# ESP32_Schem_V2.net
KiCad netlist of a schematic drawn in Altium Designer
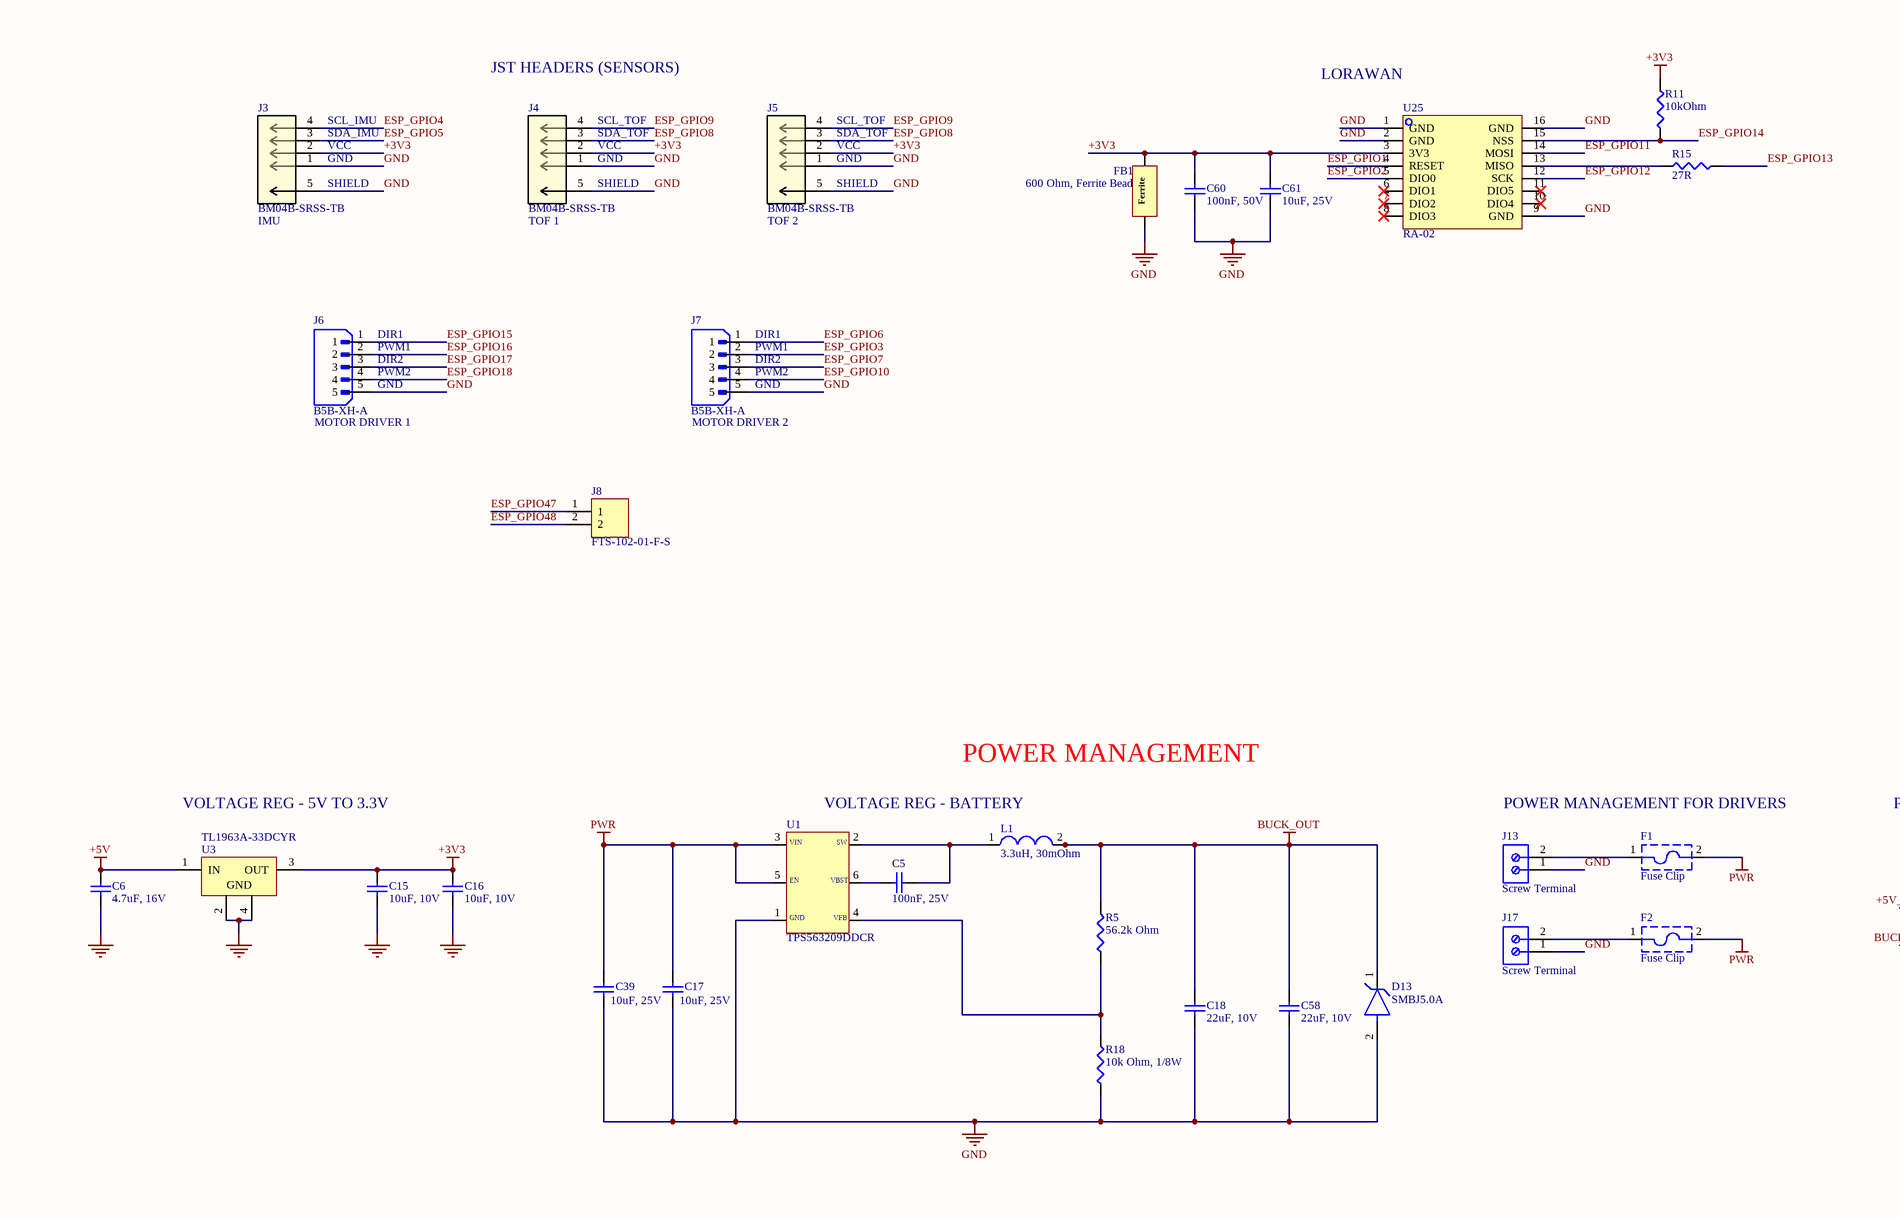
[diagram p0: ESP32_Schem_V2.SchDoc, top left]
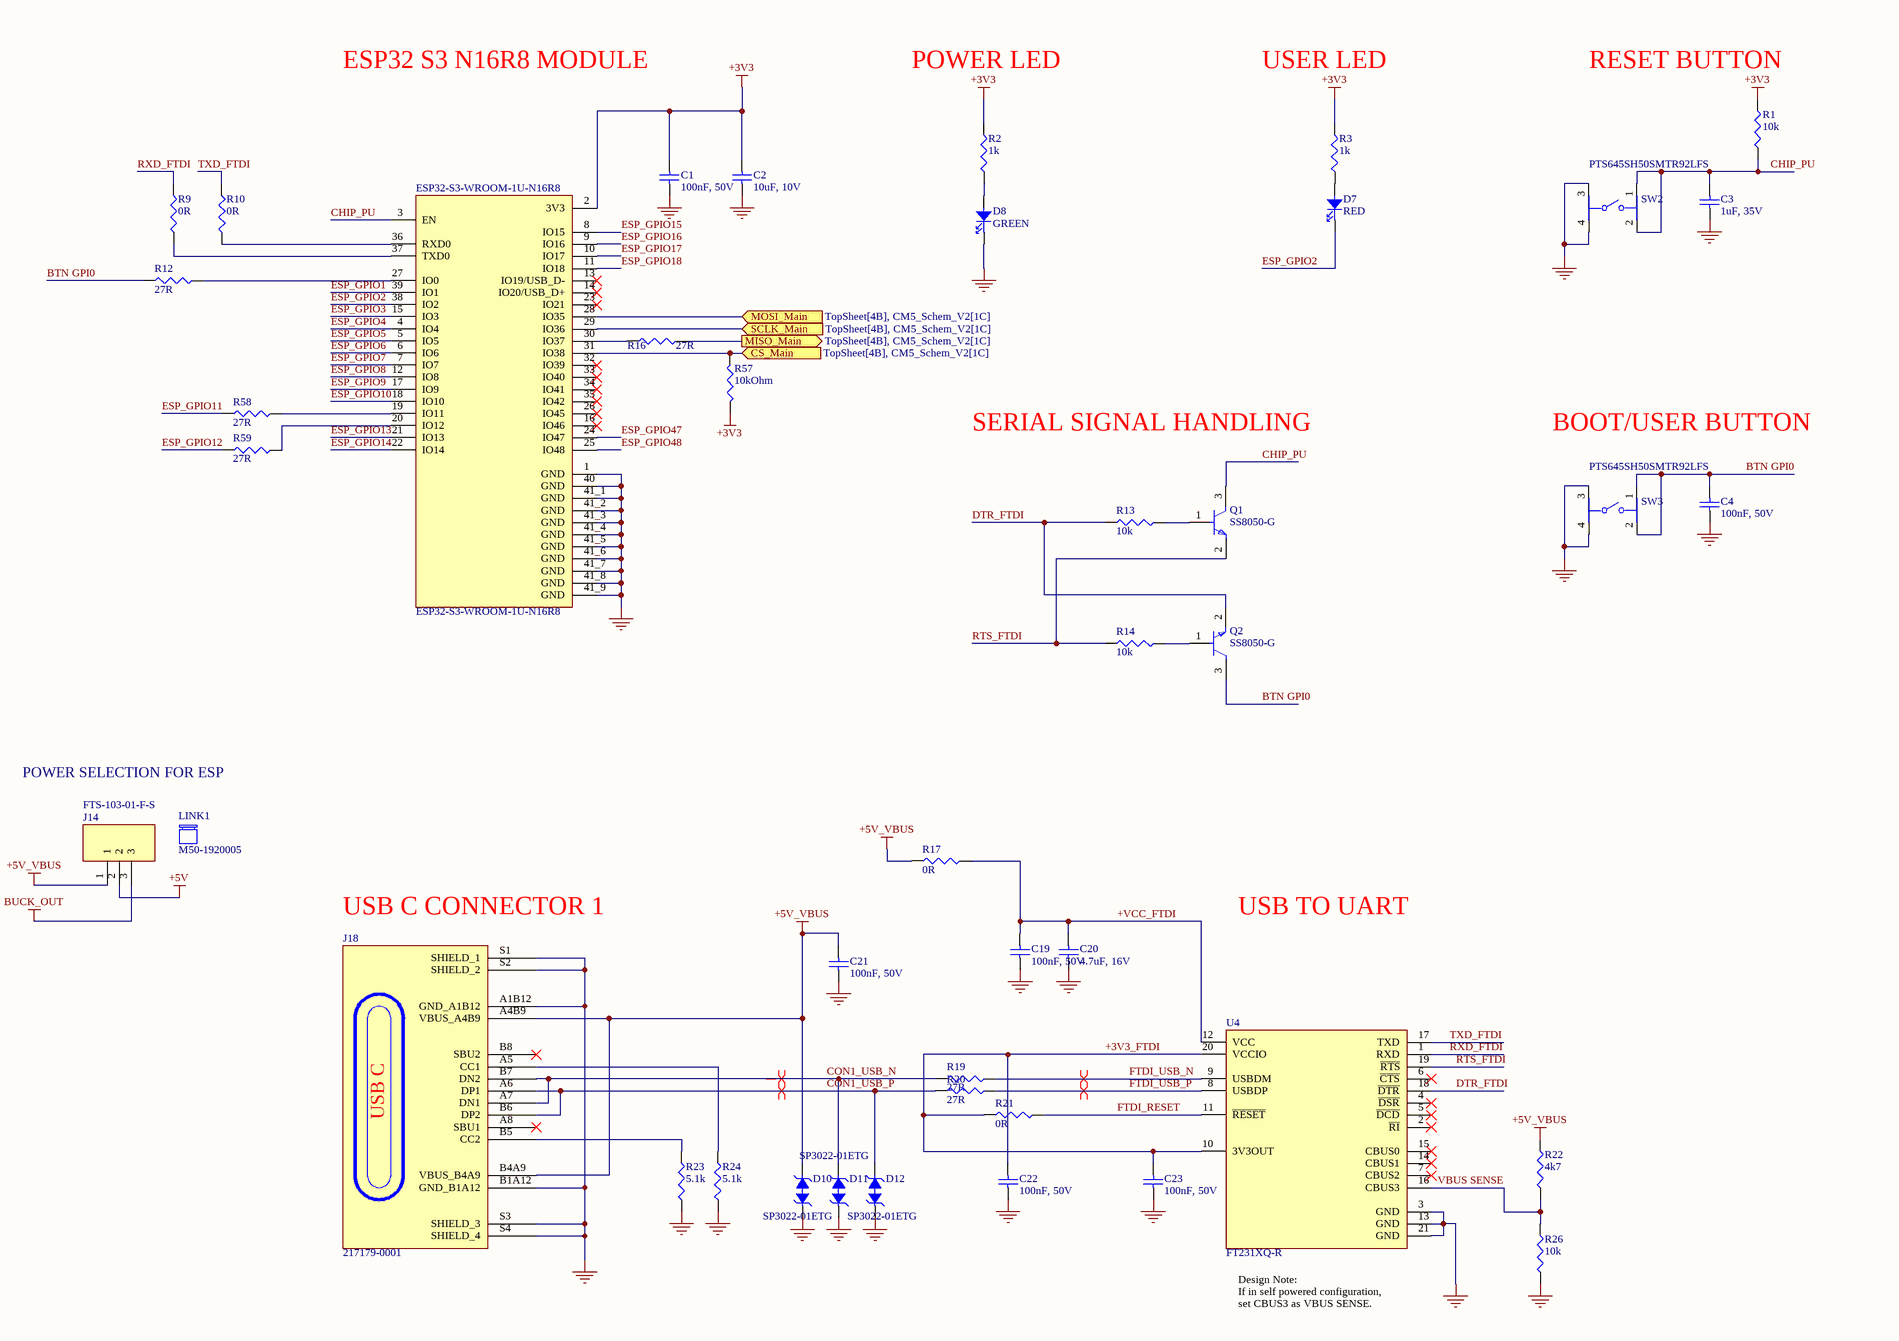
[diagram p1: ESP32_Schem_V2.SchDoc, top right]
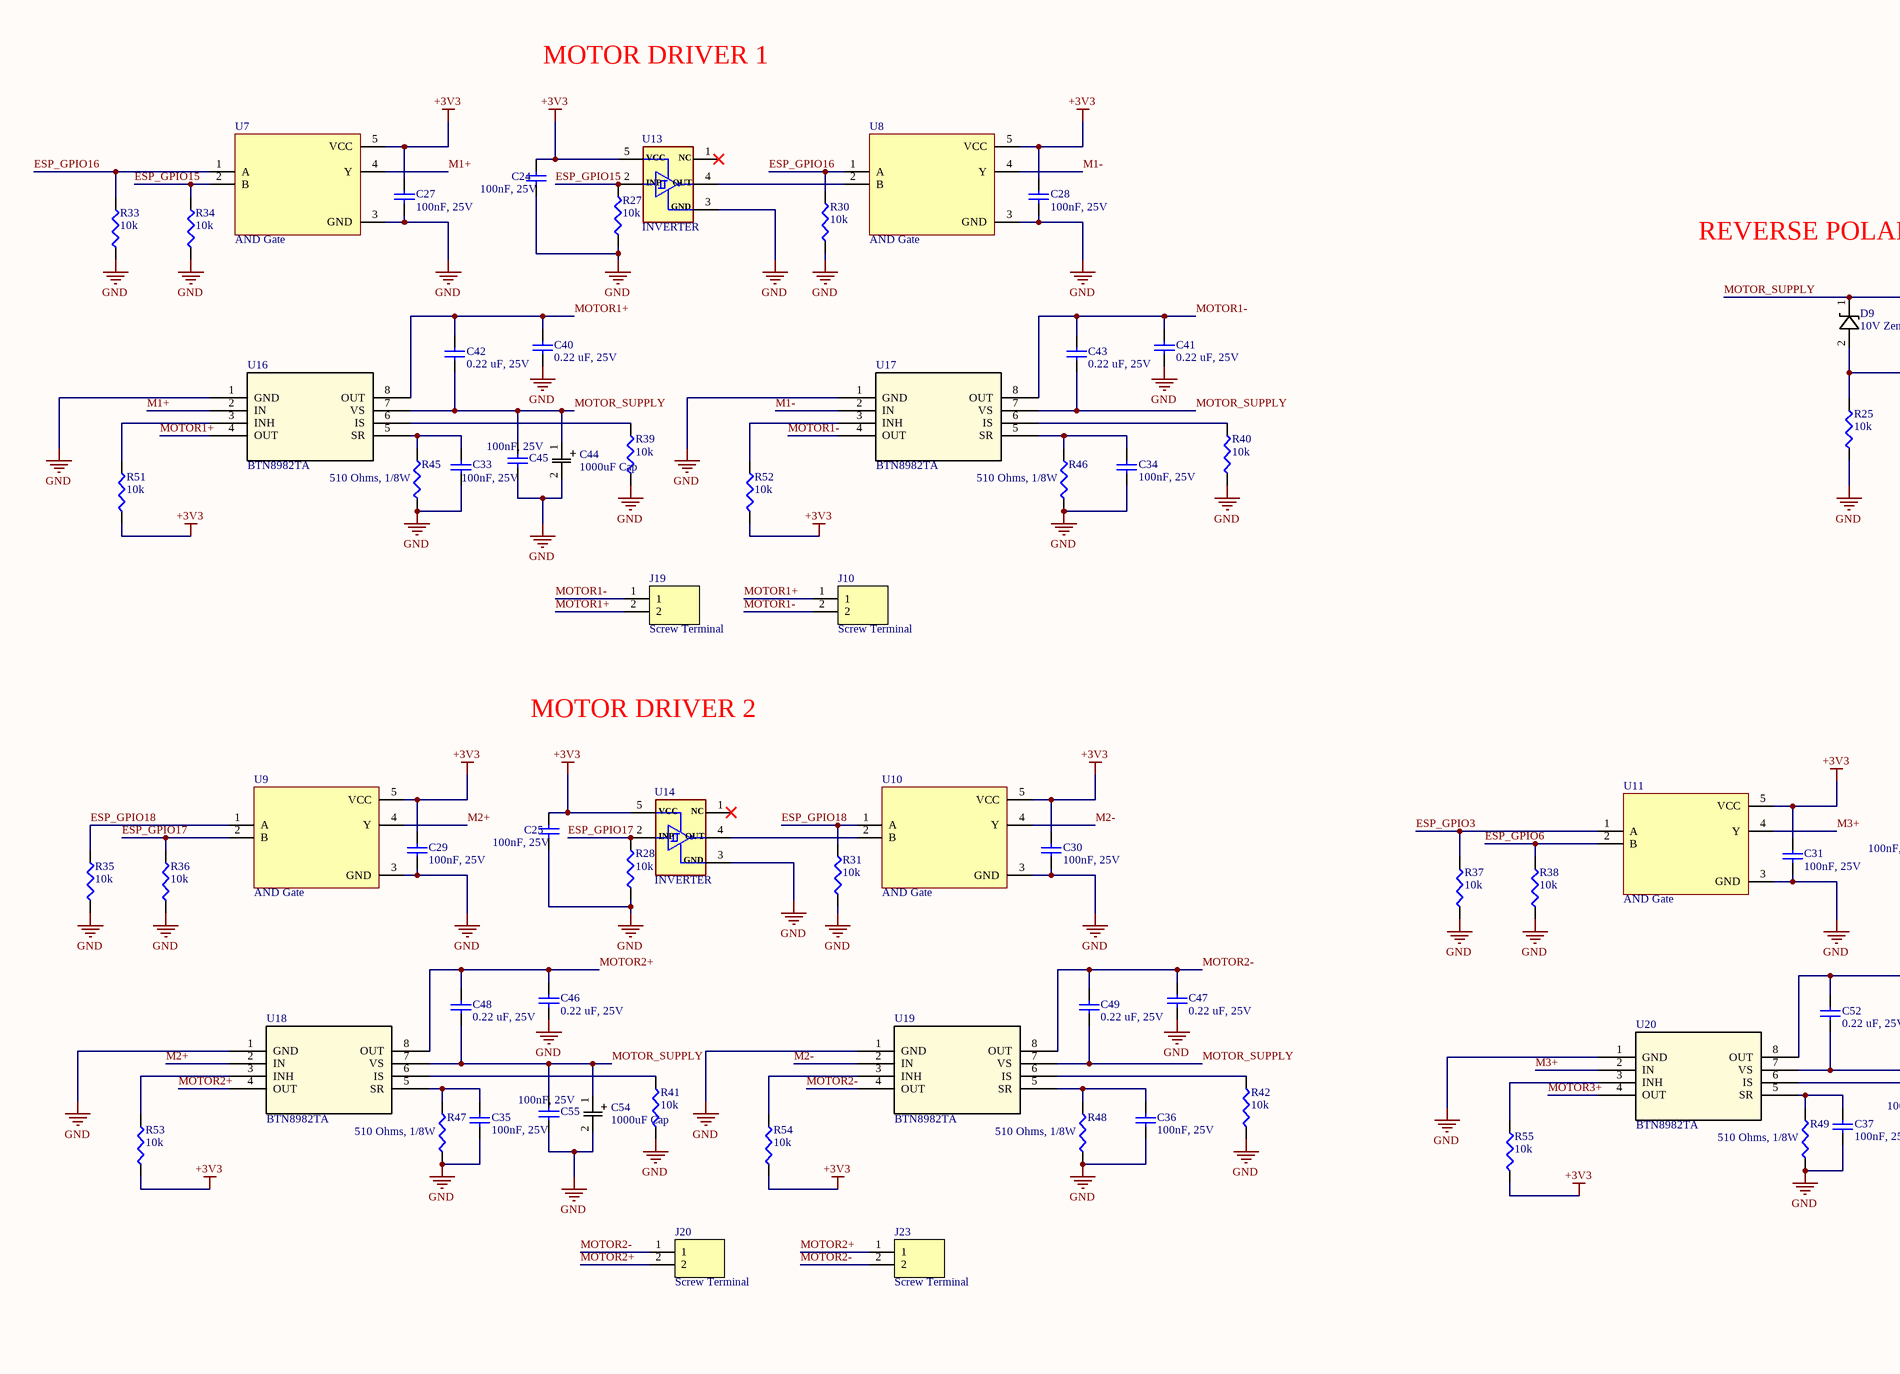
[diagram p2: ESP32_Schem_V2.SchDoc, bottom left]
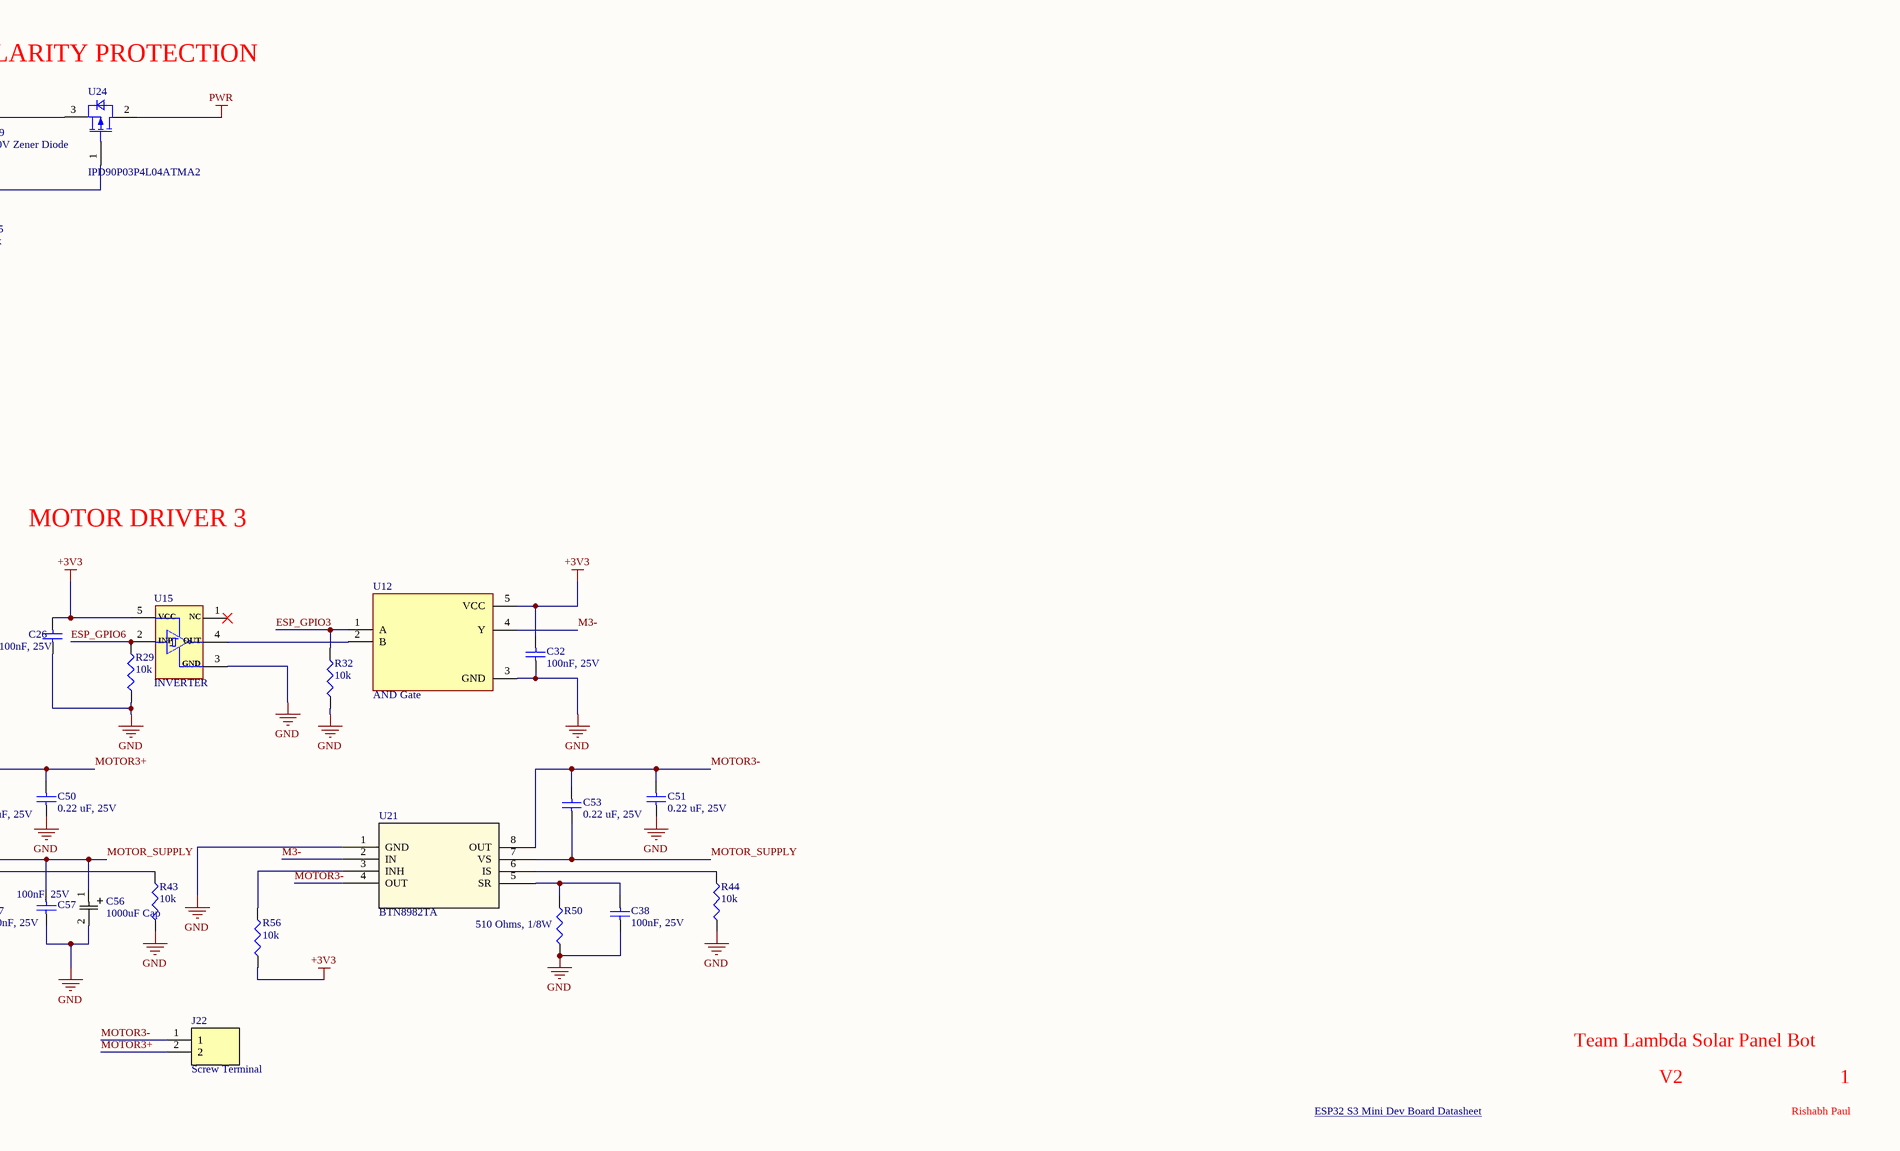
[diagram p3: ESP32_Schem_V2.SchDoc, bottom right]

(export (version "E")
  (design (tool "Eeschema 10.0.6"))
  (components
    (comp (ref "C1")
      (value "100nF, 50V")
      (footprint "CAPC1005X55N")
      (fields
        (field (name "MANUFACTURER") "Samsung")
        (field (name "MANUFACTURER PART NUMBER") "CL05B104KB54PNC")
        (field (name "LCSC PART NUMBER") "C307331")
      )
      (libsource (lib "Schlib") (part "CL05B104KB54PNC"))
    )
    (comp (ref "C2")
      (value "10uF, 10V")
      (footprint "CAPC1005X55N")
      (fields
        (field (name "MANUFACTURER") "Samsung")
        (field (name "MANUFACTURER PART NUMBER") "CL05A106MP8NUB8")
        (field (name "LCSC PART NUMBER") "C307415")
      )
      (libsource (lib "Schlib") (part "CL05A106MP8NUB8"))
    )
    (comp (ref "C3")
      (value "1uF, 35V")
      (footprint "CAPC1005X55N")
      (fields
        (field (name "MANUFACTURER") "Samsung")
        (field (name "MANUFACTURER PART NUMBER") "CL05A105KL5NRNC")
        (field (name "LCSC PART NUMBER") "C307413")
      )
      (libsource (lib "Schlib") (part "CL05A105KL5NRNC"))
    )
    (comp (ref "C4")
      (value "100nF, 50V")
      (footprint "CAPC1005X55N")
      (fields
        (field (name "MANUFACTURER") "Samsung")
        (field (name "MANUFACTURER PART NUMBER") "CL05B104KB54PNC")
        (field (name "LCSC PART NUMBER") "C307331")
      )
      (libsource (lib "Schlib") (part "CL05B104KB54PNC"))
    )
    (comp (ref "C5")
      (value "100nF, 25V")
      (footprint "CAP_X7R_0805_AVX-M")
      (description "25V 100Nf X7R 10% 0805 Multilayer Ceramic Capacitors Mlcc Smd/Smt Rohs")
      (fields
        (field (name "MANUFACTURER") "Yageo Group")
        (field (name "MANUFACTURER PART NUMBER") "CC0805KRX7R8BB104")
      )
      (libsource (lib "Schlib_CM5+ESP32") (part "CC0805KRX7R8BB104"))
    )
    (comp (ref "C6")
      (value "4.7uF, 16V")
      (footprint "CAPC1005X55N")
      (fields
        (field (name "MANUFACTURER") "Samsung")
        (field (name "MANUFACTURER PART NUMBER") "CL05A475MO5NUNC")
        (field (name "LCSC PART NUMBER") "C318563")
      )
      (libsource (lib "Schlib_PersonalProject") (part "CL05A475MO5NUNC"))
    )
    (comp (ref "C15")
      (value "10uF, 10V")
      (footprint "CAPC1005X55N")
      (fields
        (field (name "MANUFACTURER") "Samsung")
        (field (name "MANUFACTURER PART NUMBER") "CL05A106MP8NUB8")
        (field (name "LCSC PART NUMBER") "C307415")
      )
      (libsource (lib "Schlib_PersonalProject") (part "CL05A106MP8NUB8"))
    )
    (comp (ref "C16")
      (value "10uF, 10V")
      (footprint "CAPC1005X55N")
      (fields
        (field (name "MANUFACTURER") "Samsung")
        (field (name "MANUFACTURER PART NUMBER") "CL05A106MP8NUB8")
        (field (name "LCSC PART NUMBER") "C307415")
      )
      (libsource (lib "Schlib_PersonalProject") (part "CL05A106MP8NUB8"))
    )
    (comp (ref "C17")
      (value "10uF, 25V")
      (footprint "CAPC2012X95N")
      (description "CAP CER 10UF 25V X5R 0805")
      (fields
        (field (name "MANUFACTURER") "TAIYO YUDEN")
        (field (name "MANUFACTURER PART NUMBER") "TMK212BBJ106KG-T")
      )
      (libsource (lib "Schlib_CM5+ESP32") (part "TMK212BBJ106KG-T"))
    )
    (comp (ref "C18")
      (value "22uF, 10V")
      (footprint "CAP_1608_TDK-M")
      (description "CAP CER 22UF 10V X5R 0603")
      (fields
        (field (name "MANUFACTURER") "TDK")
        (field (name "MANUFACTURER PART NUMBER") "C1608X5R1A226M080AC")
      )
      (libsource (lib "Schlib_CM5+ESP32") (part "C1608X5R1A226M080AC"))
    )
    (comp (ref "C19")
      (value "100nF, 50V")
      (footprint "CAPC1005X55N")
      (fields
        (field (name "MANUFACTURER") "Samsung")
        (field (name "MANUFACTURER PART NUMBER") "CL05B104KB54PNC")
        (field (name "LCSC PART NUMBER") "C307331")
      )
      (libsource (lib "Schlib") (part "CL05B104KB54PNC"))
    )
    (comp (ref "C20")
      (value "4.7uF, 16V")
      (footprint "CAPC1005X55N")
      (fields
        (field (name "MANUFACTURER") "Samsung")
        (field (name "MANUFACTURER PART NUMBER") "CL05A475MO5NUNC")
        (field (name "LCSC PART NUMBER") "C318563")
      )
      (libsource (lib "Schlib") (part "CL05A475MO5NUNC"))
    )
    (comp (ref "C21")
      (value "100nF, 50V")
      (footprint "CAPC1005X55N")
      (fields
        (field (name "MANUFACTURER") "Samsung")
        (field (name "MANUFACTURER PART NUMBER") "CL05B104KB54PNC")
        (field (name "LCSC PART NUMBER") "C307331")
      )
      (libsource (lib "Schlib") (part "CL05B104KB54PNC"))
    )
    (comp (ref "C22")
      (value "100nF, 50V")
      (footprint "CAPC1005X55N")
      (fields
        (field (name "MANUFACTURER") "Samsung")
        (field (name "MANUFACTURER PART NUMBER") "CL05B104KB54PNC")
        (field (name "LCSC PART NUMBER") "C307331")
      )
      (libsource (lib "Schlib") (part "CL05B104KB54PNC"))
    )
    (comp (ref "C23")
      (value "100nF, 50V")
      (footprint "CAPC1005X55N")
      (fields
        (field (name "MANUFACTURER") "Samsung")
        (field (name "MANUFACTURER PART NUMBER") "CL05B104KB54PNC")
        (field (name "LCSC PART NUMBER") "C307331")
      )
      (libsource (lib "Schlib") (part "CL05B104KB54PNC"))
    )
    (comp (ref "C24")
      (value "100nF, 25V")
      (footprint "CAP_X7R_0805_AVX-M")
      (description "25V 100Nf X7R 10% 0805 Multilayer Ceramic Capacitors Mlcc Smd/Smt Rohs")
      (fields
        (field (name "MANUFACTURER") "Yageo Group")
        (field (name "MANUFACTURER PART NUMBER") "CC0805KRX7R8BB104")
      )
      (libsource (lib "Schlib_CM5+ESP32") (part "CC0805KRX7R8BB104"))
    )
    (comp (ref "C25")
      (value "100nF, 25V")
      (footprint "CAP_X7R_0805_AVX-M")
      (description "25V 100Nf X7R 10% 0805 Multilayer Ceramic Capacitors Mlcc Smd/Smt Rohs")
      (fields
        (field (name "MANUFACTURER") "Yageo Group")
        (field (name "MANUFACTURER PART NUMBER") "CC0805KRX7R8BB104")
      )
      (libsource (lib "Schlib_CM5+ESP32") (part "CC0805KRX7R8BB104"))
    )
    (comp (ref "C26")
      (value "100nF, 25V")
      (footprint "CAP_X7R_0805_AVX-M")
      (description "25V 100Nf X7R 10% 0805 Multilayer Ceramic Capacitors Mlcc Smd/Smt Rohs")
      (fields
        (field (name "MANUFACTURER") "Yageo Group")
        (field (name "MANUFACTURER PART NUMBER") "CC0805KRX7R8BB104")
      )
      (libsource (lib "Schlib_CM5+ESP32") (part "CC0805KRX7R8BB104"))
    )
    (comp (ref "C27")
      (value "100nF, 25V")
      (footprint "CAP_X7R_0805_AVX-M")
      (description "25V 100Nf X7R 10% 0805 Multilayer Ceramic Capacitors Mlcc Smd/Smt Rohs")
      (fields
        (field (name "MANUFACTURER") "Yageo Group")
        (field (name "MANUFACTURER PART NUMBER") "CC0805KRX7R8BB104")
      )
      (libsource (lib "Schlib_CM5+ESP32") (part "CC0805KRX7R8BB104"))
    )
    (comp (ref "C28")
      (value "100nF, 25V")
      (footprint "CAP_X7R_0805_AVX-M")
      (description "25V 100Nf X7R 10% 0805 Multilayer Ceramic Capacitors Mlcc Smd/Smt Rohs")
      (fields
        (field (name "MANUFACTURER") "Yageo Group")
        (field (name "MANUFACTURER PART NUMBER") "CC0805KRX7R8BB104")
      )
      (libsource (lib "Schlib_CM5+ESP32") (part "CC0805KRX7R8BB104"))
    )
    (comp (ref "C29")
      (value "100nF, 25V")
      (footprint "CAP_X7R_0805_AVX-M")
      (description "25V 100Nf X7R 10% 0805 Multilayer Ceramic Capacitors Mlcc Smd/Smt Rohs")
      (fields
        (field (name "MANUFACTURER") "Yageo Group")
        (field (name "MANUFACTURER PART NUMBER") "CC0805KRX7R8BB104")
      )
      (libsource (lib "Schlib_CM5+ESP32") (part "CC0805KRX7R8BB104"))
    )
    (comp (ref "C30")
      (value "100nF, 25V")
      (footprint "CAP_X7R_0805_AVX-M")
      (description "25V 100Nf X7R 10% 0805 Multilayer Ceramic Capacitors Mlcc Smd/Smt Rohs")
      (fields
        (field (name "MANUFACTURER") "Yageo Group")
        (field (name "MANUFACTURER PART NUMBER") "CC0805KRX7R8BB104")
      )
      (libsource (lib "Schlib_CM5+ESP32") (part "CC0805KRX7R8BB104"))
    )
    (comp (ref "C31")
      (value "100nF, 25V")
      (footprint "CAP_X7R_0805_AVX-M")
      (description "25V 100Nf X7R 10% 0805 Multilayer Ceramic Capacitors Mlcc Smd/Smt Rohs")
      (fields
        (field (name "MANUFACTURER") "Yageo Group")
        (field (name "MANUFACTURER PART NUMBER") "CC0805KRX7R8BB104")
      )
      (libsource (lib "Schlib_CM5+ESP32") (part "CC0805KRX7R8BB104"))
    )
    (comp (ref "C32")
      (value "100nF, 25V")
      (footprint "CAP_X7R_0805_AVX-M")
      (description "25V 100Nf X7R 10% 0805 Multilayer Ceramic Capacitors Mlcc Smd/Smt Rohs")
      (fields
        (field (name "MANUFACTURER") "Yageo Group")
        (field (name "MANUFACTURER PART NUMBER") "CC0805KRX7R8BB104")
      )
      (libsource (lib "Schlib_CM5+ESP32") (part "CC0805KRX7R8BB104"))
    )
    (comp (ref "C33")
      (value "100nF, 25V")
      (footprint "CAP_X7R_0805_AVX-M")
      (description "25V 100Nf X7R 10% 0805 Multilayer Ceramic Capacitors Mlcc Smd/Smt Rohs")
      (fields
        (field (name "MANUFACTURER") "Yageo Group")
        (field (name "MANUFACTURER PART NUMBER") "CC0805KRX7R8BB104")
      )
      (libsource (lib "Schlib_CM5+ESP32") (part "CC0805KRX7R8BB104"))
    )
    (comp (ref "C34")
      (value "100nF, 25V")
      (footprint "CAP_X7R_0805_AVX-M")
      (description "25V 100Nf X7R 10% 0805 Multilayer Ceramic Capacitors Mlcc Smd/Smt Rohs")
      (fields
        (field (name "MANUFACTURER") "Yageo Group")
        (field (name "MANUFACTURER PART NUMBER") "CC0805KRX7R8BB104")
      )
      (libsource (lib "Schlib_CM5+ESP32") (part "CC0805KRX7R8BB104"))
    )
    (comp (ref "C35")
      (value "100nF, 25V")
      (footprint "CAP_X7R_0805_AVX-M")
      (description "25V 100Nf X7R 10% 0805 Multilayer Ceramic Capacitors Mlcc Smd/Smt Rohs")
      (fields
        (field (name "MANUFACTURER") "Yageo Group")
        (field (name "MANUFACTURER PART NUMBER") "CC0805KRX7R8BB104")
      )
      (libsource (lib "Schlib_CM5+ESP32") (part "CC0805KRX7R8BB104"))
    )
    (comp (ref "C36")
      (value "100nF, 25V")
      (footprint "CAP_X7R_0805_AVX-M")
      (description "25V 100Nf X7R 10% 0805 Multilayer Ceramic Capacitors Mlcc Smd/Smt Rohs")
      (fields
        (field (name "MANUFACTURER") "Yageo Group")
        (field (name "MANUFACTURER PART NUMBER") "CC0805KRX7R8BB104")
      )
      (libsource (lib "Schlib_CM5+ESP32") (part "CC0805KRX7R8BB104"))
    )
    (comp (ref "C37")
      (value "100nF, 25V")
      (footprint "CAP_X7R_0805_AVX-M")
      (description "25V 100Nf X7R 10% 0805 Multilayer Ceramic Capacitors Mlcc Smd/Smt Rohs")
      (fields
        (field (name "MANUFACTURER") "Yageo Group")
        (field (name "MANUFACTURER PART NUMBER") "CC0805KRX7R8BB104")
      )
      (libsource (lib "Schlib_CM5+ESP32") (part "CC0805KRX7R8BB104"))
    )
    (comp (ref "C38")
      (value "100nF, 25V")
      (footprint "CAP_X7R_0805_AVX-M")
      (description "25V 100Nf X7R 10% 0805 Multilayer Ceramic Capacitors Mlcc Smd/Smt Rohs")
      (fields
        (field (name "MANUFACTURER") "Yageo Group")
        (field (name "MANUFACTURER PART NUMBER") "CC0805KRX7R8BB104")
      )
      (libsource (lib "Schlib_CM5+ESP32") (part "CC0805KRX7R8BB104"))
    )
    (comp (ref "C39")
      (value "10uF, 25V")
      (footprint "CAPC2012X95N")
      (description "CAP CER 10UF 25V X5R 0805")
      (fields
        (field (name "MANUFACTURER") "TAIYO YUDEN")
        (field (name "MANUFACTURER PART NUMBER") "TMK212BBJ106KG-T")
      )
      (libsource (lib "Schlib_CM5+ESP32") (part "TMK212BBJ106KG-T"))
    )
    (comp (ref "C40")
      (value "0.22 uF, 25V")
      (footprint "CAP_1608_TDK-M")
      (description "CAP CER 0.22UF 25V X7R 0603")
      (fields
        (field (name "MANUFACTURER") "Yageo Group")
        (field (name "MANUFACTURER PART NUMBER") "CC0603KRX7R8BB224")
      )
      (libsource (lib "Schlib_CM5+ESP32") (part "CC0603KRX7R8BB224"))
    )
    (comp (ref "C41")
      (value "0.22 uF, 25V")
      (footprint "CAP_1608_TDK-M")
      (description "CAP CER 0.22UF 25V X7R 0603")
      (fields
        (field (name "MANUFACTURER") "Yageo Group")
        (field (name "MANUFACTURER PART NUMBER") "CC0603KRX7R8BB224")
      )
      (libsource (lib "Schlib_CM5+ESP32") (part "CC0603KRX7R8BB224"))
    )
    (comp (ref "C42")
      (value "0.22 uF, 25V")
      (footprint "CAP_1608_TDK-M")
      (description "CAP CER 0.22UF 25V X7R 0603")
      (fields
        (field (name "MANUFACTURER") "Yageo Group")
        (field (name "MANUFACTURER PART NUMBER") "CC0603KRX7R8BB224")
      )
      (libsource (lib "Schlib_CM5+ESP32") (part "CC0603KRX7R8BB224"))
    )
    (comp (ref "C43")
      (value "0.22 uF, 25V")
      (footprint "CAP_1608_TDK-M")
      (description "CAP CER 0.22UF 25V X7R 0603")
      (fields
        (field (name "MANUFACTURER") "Yageo Group")
        (field (name "MANUFACTURER PART NUMBER") "CC0603KRX7R8BB224")
      )
      (libsource (lib "Schlib_CM5+ESP32") (part "CC0603KRX7R8BB224"))
    )
    (comp (ref "C44")
      (value "1000uF Cap")
      (footprint "CAP_PKPZ_10X20_LOW_RUB")
      (description "CAP ALUM 1000UF 20% 35V RADIAL")
      (fields
        (field (name "MANUFACTURER") "Rubycon")
        (field (name "MANUFACTURER PART NUMBER") "35PX1000MEFC10X20")
      )
      (libsource (lib "Schlib_CM5+ESP32") (part "35PX1000MEFC10X20"))
    )
    (comp (ref "C45")
      (value "100nF, 25V")
      (footprint "CAP_X7R_0805_AVX-M")
      (description "25V 100Nf X7R 10% 0805 Multilayer Ceramic Capacitors Mlcc Smd/Smt Rohs")
      (fields
        (field (name "MANUFACTURER") "Yageo Group")
        (field (name "MANUFACTURER PART NUMBER") "CC0805KRX7R8BB104")
      )
      (libsource (lib "Schlib_CM5+ESP32") (part "CC0805KRX7R8BB104"))
    )
    (comp (ref "C46")
      (value "0.22 uF, 25V")
      (footprint "CAP_1608_TDK-M")
      (description "CAP CER 0.22UF 25V X7R 0603")
      (fields
        (field (name "MANUFACTURER") "Yageo Group")
        (field (name "MANUFACTURER PART NUMBER") "CC0603KRX7R8BB224")
      )
      (libsource (lib "Schlib_CM5+ESP32") (part "CC0603KRX7R8BB224"))
    )
    (comp (ref "C47")
      (value "0.22 uF, 25V")
      (footprint "CAP_1608_TDK-M")
      (description "CAP CER 0.22UF 25V X7R 0603")
      (fields
        (field (name "MANUFACTURER") "Yageo Group")
        (field (name "MANUFACTURER PART NUMBER") "CC0603KRX7R8BB224")
      )
      (libsource (lib "Schlib_CM5+ESP32") (part "CC0603KRX7R8BB224"))
    )
    (comp (ref "C48")
      (value "0.22 uF, 25V")
      (footprint "CAP_1608_TDK-M")
      (description "CAP CER 0.22UF 25V X7R 0603")
      (fields
        (field (name "MANUFACTURER") "Yageo Group")
        (field (name "MANUFACTURER PART NUMBER") "CC0603KRX7R8BB224")
      )
      (libsource (lib "Schlib_CM5+ESP32") (part "CC0603KRX7R8BB224"))
    )
    (comp (ref "C49")
      (value "0.22 uF, 25V")
      (footprint "CAP_1608_TDK-M")
      (description "CAP CER 0.22UF 25V X7R 0603")
      (fields
        (field (name "MANUFACTURER") "Yageo Group")
        (field (name "MANUFACTURER PART NUMBER") "CC0603KRX7R8BB224")
      )
      (libsource (lib "Schlib_CM5+ESP32") (part "CC0603KRX7R8BB224"))
    )
    (comp (ref "C50")
      (value "0.22 uF, 25V")
      (footprint "CAP_1608_TDK-M")
      (description "CAP CER 0.22UF 25V X7R 0603")
      (fields
        (field (name "MANUFACTURER") "Yageo Group")
        (field (name "MANUFACTURER PART NUMBER") "CC0603KRX7R8BB224")
      )
      (libsource (lib "Schlib_CM5+ESP32") (part "CC0603KRX7R8BB224"))
    )
    (comp (ref "C51")
      (value "0.22 uF, 25V")
      (footprint "CAP_1608_TDK-M")
      (description "CAP CER 0.22UF 25V X7R 0603")
      (fields
        (field (name "MANUFACTURER") "Yageo Group")
        (field (name "MANUFACTURER PART NUMBER") "CC0603KRX7R8BB224")
      )
      (libsource (lib "Schlib_CM5+ESP32") (part "CC0603KRX7R8BB224"))
    )
    (comp (ref "C52")
      (value "0.22 uF, 25V")
      (footprint "CAP_1608_TDK-M")
      (description "CAP CER 0.22UF 25V X7R 0603")
      (fields
        (field (name "MANUFACTURER") "Yageo Group")
        (field (name "MANUFACTURER PART NUMBER") "CC0603KRX7R8BB224")
      )
      (libsource (lib "Schlib_CM5+ESP32") (part "CC0603KRX7R8BB224"))
    )
    (comp (ref "C53")
      (value "0.22 uF, 25V")
      (footprint "CAP_1608_TDK-M")
      (description "CAP CER 0.22UF 25V X7R 0603")
      (fields
        (field (name "MANUFACTURER") "Yageo Group")
        (field (name "MANUFACTURER PART NUMBER") "CC0603KRX7R8BB224")
      )
      (libsource (lib "Schlib_CM5+ESP32") (part "CC0603KRX7R8BB224"))
    )
    (comp (ref "C54")
      (value "1000uF Cap")
      (footprint "CAP_PKPZ_10X20_LOW_RUB")
      (description "CAP ALUM 1000UF 20% 35V RADIAL")
      (fields
        (field (name "MANUFACTURER") "Rubycon")
        (field (name "MANUFACTURER PART NUMBER") "35PX1000MEFC10X20")
      )
      (libsource (lib "Schlib_CM5+ESP32") (part "35PX1000MEFC10X20"))
    )
    (comp (ref "C55")
      (value "100nF, 25V")
      (footprint "CAP_X7R_0805_AVX-M")
      (description "25V 100Nf X7R 10% 0805 Multilayer Ceramic Capacitors Mlcc Smd/Smt Rohs")
      (fields
        (field (name "MANUFACTURER") "Yageo Group")
        (field (name "MANUFACTURER PART NUMBER") "CC0805KRX7R8BB104")
      )
      (libsource (lib "Schlib_CM5+ESP32") (part "CC0805KRX7R8BB104"))
    )
    (comp (ref "C56")
      (value "1000uF Cap")
      (footprint "CAP_PKPZ_10X20_LOW_RUB")
      (description "CAP ALUM 1000UF 20% 35V RADIAL")
      (fields
        (field (name "MANUFACTURER") "Rubycon")
        (field (name "MANUFACTURER PART NUMBER") "35PX1000MEFC10X20")
      )
      (libsource (lib "Schlib_CM5+ESP32") (part "35PX1000MEFC10X20"))
    )
    (comp (ref "C57")
      (value "100nF, 25V")
      (footprint "CAP_X7R_0805_AVX-M")
      (description "25V 100Nf X7R 10% 0805 Multilayer Ceramic Capacitors Mlcc Smd/Smt Rohs")
      (fields
        (field (name "MANUFACTURER") "Yageo Group")
        (field (name "MANUFACTURER PART NUMBER") "CC0805KRX7R8BB104")
      )
      (libsource (lib "Schlib_CM5+ESP32") (part "CC0805KRX7R8BB104"))
    )
    (comp (ref "C58")
      (value "22uF, 10V")
      (footprint "CAP_1608_TDK-M")
      (description "CAP CER 22UF 10V X5R 0603")
      (fields
        (field (name "MANUFACTURER") "TDK")
        (field (name "MANUFACTURER PART NUMBER") "C1608X5R1A226M080AC")
      )
      (libsource (lib "Schlib_CM5+ESP32") (part "C1608X5R1A226M080AC"))
    )
    (comp (ref "C60")
      (value "100nF, 50V")
      (footprint "CAPC1005X55N")
      (fields
        (field (name "MANUFACTURER") "Samsung")
        (field (name "MANUFACTURER PART NUMBER") "CL05B104KB54PNC")
        (field (name "LCSC PART NUMBER") "C307331")
      )
      (libsource (lib "Schlib") (part "CL05B104KB54PNC"))
    )
    (comp (ref "C61")
      (value "10uF, 25V")
      (footprint "CAPC2012X95N")
      (description "CAP CER 10UF 25V X5R 0805")
      (fields
        (field (name "MANUFACTURER") "TAIYO YUDEN")
        (field (name "MANUFACTURER PART NUMBER") "TMK212BBJ106KG-T")
      )
      (libsource (lib "Schlib_CM5+ESP32") (part "TMK212BBJ106KG-T"))
    )
    (comp (ref "D7")
      (value "RED")
      (footprint "LED0402R")
      (description "Single Color LED, Super Red, 0.5mm")
      (fields
        (field (name "MANUFACTURER") "Vishay")
        (field (name "MANUFACTURER PART NUMBER") "VLMS1500-GS08")
      )
      (libsource (lib "Schlib") (part "VLMS1500-GS08"))
    )
    (comp (ref "D8")
      (value "GREEN")
      (footprint "LED0402G")
      (description "Single Color LED, Yellow Green, 0.5mm")
      (fields
        (field (name "MANUFACTURER") "Vishay")
        (field (name "MANUFACTURER PART NUMBER") "VLMG1500-GS08")
      )
      (libsource (lib "Schlib") (part "VLMG1500-GS08"))
    )
    (comp (ref "D9")
      (value "10V Zener Diode")
      (footprint "CR_BZT52_DIO")
      (description "Zener Diode, 10V, 0.25W, X1-Dfn1006 Rohs Compliant: Yes ¦Diodes Inc. BZT52C10LP-7")
      (fields
        (field (name "MANUFACTURER") "Diodes Inc.")
        (field (name "MANUFACTURER PART NUMBER") "BZT52C10LP-7")
      )
      (libsource (lib "Schlib_CM5+ESP32") (part "BZT52C10LP-7"))
    )
    (comp (ref "D10")
      (value "SP3022-01ETG")
      (footprint "SOD882")
      (description "TVS DIODE 5.3VWM 12VC SOD882")
      (fields (field (name "MANUFACTURER") "Littelfuse") (field (name "LCSC PART NUMBER") "C126840"))
      (libsource (lib "Schlib_CM5+ESP32") (part "SP3022-01ETG"))
    )
    (comp (ref "D11")
      (value "SP3022-01ETG")
      (footprint "SOD882")
      (description "TVS DIODE 5.3VWM 12VC SOD882")
      (fields (field (name "MANUFACTURER") "Littelfuse") (field (name "LCSC PART NUMBER") "C126840"))
      (libsource (lib "Schlib_CM5+ESP32") (part "SP3022-01ETG"))
    )
    (comp (ref "D12")
      (value "SP3022-01ETG")
      (footprint "SOD882")
      (description "TVS DIODE 5.3VWM 12VC SOD882")
      (fields (field (name "MANUFACTURER") "Littelfuse") (field (name "LCSC PART NUMBER") "C126840"))
      (libsource (lib "Schlib_CM5+ESP32") (part "SP3022-01ETG"))
    )
    (comp (ref "D13")
      (value "SMBJ5.0A")
      (footprint "DO-214AASMB_J-BEND_LTF-M")
      (description "TVS DIODE 5VWM 9.2VC DO214AA")
      (fields (field (name "MANUFACTURER") "Littelfuse") (field (name "LCSC PART NUMBER") "C83333"))
      (libsource (lib "Schlib_CM5+ESP32") (part "SMBJ5.0A"))
    )
    (comp (ref "ESP32-S3-WROOM-1U-N16R8")
      (value "ESP32-S3-WROOM-1U-N16R8")
      (footprint "XCVR_ESP32-S3-WROOM-1U-N16R8")
      (fields (field (name "MANUFACTURER") "Espressif Systems") (field (name "LCSC PART NUMBER") "C49164661"))
      (libsource (lib "Schlib_CM5+ESP32") (part "ESP32-S3-WROOM-1U-N16R8"))
    )
    (comp (ref "F1")
      (value "Fuse Clip")
      (footprint "696108003002")
      (description "Fuses/Accessories")
      (fields
        (field (name "MANUFACTURER") "Wurth Electronics")
        (field (name "MANUFACTURER PART NUMBER") "696108003002")
      )
      (libsource (lib "Schlib_CM5+ESP32") (part "696108003002"))
    )
    (comp (ref "F2")
      (value "Fuse Clip")
      (footprint "696108003002")
      (description "Fuses/Accessories")
      (fields
        (field (name "MANUFACTURER") "Wurth Electronics")
        (field (name "MANUFACTURER PART NUMBER") "696108003002")
      )
      (libsource (lib "Schlib_CM5+ESP32") (part "696108003002"))
    )
    (comp (ref "FB1")
      (value "600 Ohm, Ferrite Bead")
      (footprint "BEADC1608X95N")
      (description "FERRITE BEAD 600 OHM 0603 1LN")
      (fields
        (field (name "MANUFACTURER") "Murata")
        (field (name "MANUFACTURER PART NUMBER") "BLM18AG601SN1D")
      )
      (libsource (lib "Schlib_CM5+ESP32") (part "BLM18AG601SN1D"))
    )
    (comp (ref "J3")
      (value "BM04B-SRSS-TB")
      (footprint "CONN4_BM04B-SRSS_JST")
      (description "CONN HEADER SMD 4POS 1MM")
      (fields (field (name "MANUFACTURER") "JST") (field (name "LCSC PART NUMBER") "C160390"))
      (libsource (lib "Schlib_CM5+ESP32") (part "BM04B-SRSS-TB"))
    )
    (comp (ref "J4")
      (value "BM04B-SRSS-TB")
      (footprint "CONN4_BM04B-SRSS_JST")
      (description "CONN HEADER SMD 4POS 1MM")
      (fields (field (name "MANUFACTURER") "JST") (field (name "LCSC PART NUMBER") "C160390"))
      (libsource (lib "Schlib_CM5+ESP32") (part "BM04B-SRSS-TB"))
    )
    (comp (ref "J5")
      (value "BM04B-SRSS-TB")
      (footprint "CONN4_BM04B-SRSS_JST")
      (description "CONN HEADER SMD 4POS 1MM")
      (fields (field (name "MANUFACTURER") "JST") (field (name "LCSC PART NUMBER") "C160390"))
      (libsource (lib "Schlib_CM5+ESP32") (part "BM04B-SRSS-TB"))
    )
    (comp (ref "J6")
      (value "B5B-XH-A")
      (footprint "JST_B5B-XH-A")
      (description "CONN HEADER VERT 5POS 2.5MM")
      (fields (field (name "MANUFACTURER") "JST") (field (name "LCSC PART NUMBER") "C157991"))
      (libsource (lib "Schlib_CM5+ESP32") (part "B5B-XH-A"))
    )
    (comp (ref "J7")
      (value "B5B-XH-A")
      (footprint "JST_B5B-XH-A")
      (description "CONN HEADER VERT 5POS 2.5MM")
      (fields (field (name "MANUFACTURER") "JST") (field (name "LCSC PART NUMBER") "C157991"))
      (libsource (lib "Schlib_CM5+ESP32") (part "B5B-XH-A"))
    )
    (comp (ref "J8")
      (value "FTS-102-01-F-S")
      (footprint "HDR_1x2_1.27MM")
      (description "Board Connector, 2 Contact(s), 1 Row(s), Male, Straight, Solder Terminal")
      (fields (field (name "MANUFACTURER") "Samtec") (field (name "LCSC PART NUMBER") "C6045317"))
      (libsource (lib "Schlib") (part "FTS-102-01-F-S"))
    )
    (comp (ref "J10")
      (value "Screw Terminal")
      (footprint "CUI_TB005-762-02BE")
      (description "2~24 Poles, Screw Type, Horizontal, 7.62 Pitch, 26~10 (AWG), Terminal Block Connector")
      (fields
        (field (name "MANUFACTURER") "Same Sky")
        (field (name "MANUFACTURER PART NUMBER") "TB005-762-02BE")
      )
      (libsource (lib "Schlib_CM5+ESP32") (part "TB005-762-02BE"))
    )
    (comp (ref "J13")
      (value "Screw Terminal")
      (footprint "PHOENIX_1725656")
      (description "Block, Terminal; 6 A; 63 V; 2.54 mm; 26 to 20 AWG; 2; Screw; Soldering; 1.5 kV")
      (fields
        (field (name "MANUFACTURER") "Phoenix Contact")
        (field (name "MANUFACTURER PART NUMBER") "1725656")
      )
      (libsource (lib "Schlib_CM5+ESP32") (part "1725656"))
    )
    (comp (ref "J14")
      (value "FTS-103-01-F-S")
      (footprint "HDR_1x3_1.27MM")
      (description "Board Connector, 3 Contact(s), 1 Row(s), Male, Straight, Solder Terminal")
      (fields (field (name "MANUFACTURER") "Samtec") (field (name "LCSC PART NUMBER") "C3333578"))
      (libsource (lib "Schlib") (part "FTS-103-01-F-S"))
    )
    (comp (ref "J17")
      (value "Screw Terminal")
      (footprint "PHOENIX_1725656")
      (description "Block, Terminal; 6 A; 63 V; 2.54 mm; 26 to 20 AWG; 2; Screw; Soldering; 1.5 kV")
      (fields
        (field (name "MANUFACTURER") "Phoenix Contact")
        (field (name "MANUFACTURER PART NUMBER") "1725656")
      )
      (libsource (lib "Schlib_CM5+ESP32") (part "1725656"))
    )
    (comp (ref "J18")
      (value "217179-0001")
      (footprint "FP-2171790001-MFG")
      (description "USB Connector, 16 Contact(s), Female, Right Angle, Surface Mount Terminal, Locking, Receptacle")
      (fields (field (name "MANUFACTURER") "Molex") (field (name "LCSC PART NUMBER") "C3197684"))
      (libsource (lib "Schlib") (part "217179-0001"))
    )
    (comp (ref "J19")
      (value "Screw Terminal")
      (footprint "CUI_TB005-762-02BE")
      (description "2~24 Poles, Screw Type, Horizontal, 7.62 Pitch, 26~10 (AWG), Terminal Block Connector")
      (fields
        (field (name "MANUFACTURER") "Same Sky")
        (field (name "MANUFACTURER PART NUMBER") "TB005-762-02BE")
      )
      (libsource (lib "Schlib_CM5+ESP32") (part "TB005-762-02BE"))
    )
    (comp (ref "J20")
      (value "Screw Terminal")
      (footprint "CUI_TB005-762-02BE")
      (description "2~24 Poles, Screw Type, Horizontal, 7.62 Pitch, 26~10 (AWG), Terminal Block Connector")
      (fields
        (field (name "MANUFACTURER") "Same Sky")
        (field (name "MANUFACTURER PART NUMBER") "TB005-762-02BE")
      )
      (libsource (lib "Schlib_CM5+ESP32") (part "TB005-762-02BE"))
    )
    (comp (ref "J22")
      (value "Screw Terminal")
      (footprint "CUI_TB005-762-02BE")
      (description "2~24 Poles, Screw Type, Horizontal, 7.62 Pitch, 26~10 (AWG), Terminal Block Connector")
      (fields
        (field (name "MANUFACTURER") "Same Sky")
        (field (name "MANUFACTURER PART NUMBER") "TB005-762-02BE")
      )
      (libsource (lib "Schlib_CM5+ESP32") (part "TB005-762-02BE"))
    )
    (comp (ref "J23")
      (value "Screw Terminal")
      (footprint "CUI_TB005-762-02BE")
      (description "2~24 Poles, Screw Type, Horizontal, 7.62 Pitch, 26~10 (AWG), Terminal Block Connector")
      (fields
        (field (name "MANUFACTURER") "Same Sky")
        (field (name "MANUFACTURER PART NUMBER") "TB005-762-02BE")
      )
      (libsource (lib "Schlib_CM5+ESP32") (part "TB005-762-02BE"))
    )
    (comp (ref "L1")
      (value "3.3uH, 30mOhm")
      (footprint "IND_VLS6045EX-3R3N")
      (description "FIXED IND 3.3UH 4.95A 30MOHM SMD")
      (fields (field (name "MANUFACTURER") "TDK") (field (name "MANUFACTURER PART NUMBER") "VLS6045EX-3R3N"))
      (libsource (lib "Schlib_CM5+ESP32") (part "VLS6045EX-3R3N"))
    )
    (comp (ref "LINK1")
      (value "M50-1920005")
      (description "Interconnection Device")
      (fields (field (name "MANUFACTURER") "Harwin") (field (name "LCSC PART NUMBER") "C6985646"))
      (libsource (lib "Schlib") (part "M50-1920005"))
    )
    (comp (ref "Q1")
      (value "SS8050-G")
      (footprint "FP-SS8050-G-IPC_B")
      (description "Small Signal Bipolar Transistor, 1.5A I(C), 25V V(BR)CEO, 1-Element, NPN, Silicon")
      (fields (field (name "MANUFACTURER") "Comchip") (field (name "LCSC PART NUMBER") "C164886"))
      (libsource (lib "Schlib") (part "SS8050-G"))
    )
    (comp (ref "Q2")
      (value "SS8050-G")
      (footprint "FP-SS8050-G-IPC_B")
      (description "Small Signal Bipolar Transistor, 1.5A I(C), 25V V(BR)CEO, 1-Element, NPN, Silicon")
      (fields (field (name "MANUFACTURER") "Comchip") (field (name "LCSC PART NUMBER") "C164886"))
      (libsource (lib "Schlib") (part "SS8050-G"))
    )
    (comp (ref "R1")
      (value "10k")
      (footprint "RESC1005X37N")
      (fields
        (field (name "MANUFACTURER") "Yageo")
        (field (name "MANUFACTURER PART NUMBER") "AC0402FR-0710KL")
        (field (name "TOLERANCE") "1%")
      )
      (libsource (lib "Schlib") (part "AC0402FR-0710KL"))
    )
    (comp (ref "R2")
      (value "1k")
      (footprint "RESC1005X37N")
      (fields
        (field (name "MANUFACTURER") "Yageo")
        (field (name "MANUFACTURER PART NUMBER") "RC0402FR-071KL")
        (field (name "TOLERANCE") "1%")
      )
      (libsource (lib "Schlib") (part "RC0402FR-071KL"))
    )
    (comp (ref "R3")
      (value "1k")
      (footprint "RESC1005X37N")
      (fields
        (field (name "MANUFACTURER") "Yageo")
        (field (name "MANUFACTURER PART NUMBER") "RC0402FR-071KL")
        (field (name "TOLERANCE") "1%")
      )
      (libsource (lib "Schlib") (part "RC0402FR-071KL"))
    )
    (comp (ref "R5")
      (value "56.2k Ohm")
      (footprint "RESC0603X26N")
      (description "RES 56.2K OHM 1% 1/20W 0201")
      (fields
        (field (name "MANUFACTURER") "Yageo")
        (field (name "MANUFACTURER PART NUMBER") "RC0201FR-0756K2L")
      )
      (libsource (lib "Schlib_CM5+ESP32") (part "RC0201FR-0756K2L"))
    )
    (comp (ref "R9")
      (value "0R")
      (footprint "RESC1005X37N")
      (description "Fixed Resistor, Metal Glaze/thick Film, 0.0625W, 0ohm, Surface Mount, 0402")
      (fields
        (field (name "MANUFACTURER") "Yageo")
        (field (name "MANUFACTURER PART NUMBER") "RC0402FR-070RL")
      )
      (libsource (lib "Schlib") (part "RC0402FR-070RL"))
    )
    (comp (ref "R10")
      (value "0R")
      (footprint "RESC1005X37N")
      (description "Fixed Resistor, Metal Glaze/thick Film, 0.0625W, 0ohm, Surface Mount, 0402")
      (fields
        (field (name "MANUFACTURER") "Yageo")
        (field (name "MANUFACTURER PART NUMBER") "RC0402FR-070RL")
      )
      (libsource (lib "Schlib") (part "RC0402FR-070RL"))
    )
    (comp (ref "R11")
      (value "10kOhm")
      (footprint "RESC0603X26N - duplicate")
      (description "RES 10K OHM 1% 1/20W 0201")
      (fields
        (field (name "MANUFACTURER") "Yageo")
        (field (name "MANUFACTURER PART NUMBER") "RC0201FR-0710KL")
      )
      (libsource (lib "Schlib_CM5+ESP32") (part "RC0201FR-0710KL"))
    )
    (comp (ref "R12")
      (value "27R")
      (footprint "RESC1005X37N")
      (fields
        (field (name "MANUFACTURER") "Yageo")
        (field (name "MANUFACTURER PART NUMBER") "RC0402FR-0727RL")
        (field (name "TOLERANCE") "1%")
      )
      (libsource (lib "Schlib") (part "RC0402FR-0727RL"))
    )
    (comp (ref "R13")
      (value "10k")
      (footprint "RESC1005X37N")
      (fields
        (field (name "MANUFACTURER") "Yageo")
        (field (name "MANUFACTURER PART NUMBER") "AC0402FR-0710KL")
        (field (name "TOLERANCE") "1%")
      )
      (libsource (lib "Schlib") (part "AC0402FR-0710KL"))
    )
    (comp (ref "R14")
      (value "10k")
      (footprint "RESC1005X37N")
      (fields
        (field (name "MANUFACTURER") "Yageo")
        (field (name "MANUFACTURER PART NUMBER") "AC0402FR-0710KL")
        (field (name "TOLERANCE") "1%")
      )
      (libsource (lib "Schlib") (part "AC0402FR-0710KL"))
    )
    (comp (ref "R15")
      (value "27R")
      (footprint "RESC1005X37N")
      (fields
        (field (name "MANUFACTURER") "Yageo")
        (field (name "MANUFACTURER PART NUMBER") "RC0402FR-0727RL")
        (field (name "TOLERANCE") "1%")
      )
      (libsource (lib "Schlib") (part "RC0402FR-0727RL"))
    )
    (comp (ref "R16")
      (value "27R")
      (footprint "RESC1005X37N")
      (fields
        (field (name "MANUFACTURER") "Yageo")
        (field (name "MANUFACTURER PART NUMBER") "RC0402FR-0727RL")
        (field (name "TOLERANCE") "1%")
      )
      (libsource (lib "Schlib") (part "RC0402FR-0727RL"))
    )
    (comp (ref "R17")
      (value "0R")
      (footprint "RESC1005X37N")
      (description "Fixed Resistor, Metal Glaze/thick Film, 0.0625W, 0ohm, Surface Mount, 0402")
      (fields
        (field (name "MANUFACTURER") "Yageo")
        (field (name "MANUFACTURER PART NUMBER") "RC0402FR-070RL")
      )
      (libsource (lib "Schlib") (part "RC0402FR-070RL"))
    )
    (comp (ref "R18")
      (value "10k Ohm, 1/8W")
      (footprint "RESC1005X40N")
      (description "RES 10K OHM 1% 1/8W 0402")
      (fields
        (field (name "MANUFACTURER") "Yageo Group")
        (field (name "MANUFACTURER PART NUMBER") "RC0402FR-7W10KL")
      )
      (libsource (lib "Schlib_CM5+ESP32") (part "RC0402FR-7W10KL"))
    )
    (comp (ref "R19")
      (value "27R")
      (footprint "RESC1005X37N")
      (fields
        (field (name "MANUFACTURER") "Yageo")
        (field (name "MANUFACTURER PART NUMBER") "RC0402FR-0727RL")
        (field (name "TOLERANCE") "1%")
      )
      (libsource (lib "Schlib") (part "RC0402FR-0727RL"))
    )
    (comp (ref "R20")
      (value "27R")
      (footprint "RESC1005X37N")
      (fields
        (field (name "MANUFACTURER") "Yageo")
        (field (name "MANUFACTURER PART NUMBER") "RC0402FR-0727RL")
        (field (name "TOLERANCE") "1%")
      )
      (libsource (lib "Schlib") (part "RC0402FR-0727RL"))
    )
    (comp (ref "R21")
      (value "0R")
      (footprint "RESC1005X37N")
      (description "Fixed Resistor, Metal Glaze/thick Film, 0.0625W, 0ohm, Surface Mount, 0402")
      (fields
        (field (name "MANUFACTURER") "Yageo")
        (field (name "MANUFACTURER PART NUMBER") "RC0402FR-070RL")
      )
      (libsource (lib "Schlib") (part "RC0402FR-070RL"))
    )
    (comp (ref "R22")
      (value "4k7")
      (footprint "RESC1005X37N")
      (fields
        (field (name "MANUFACTURER") "Yageo")
        (field (name "MANUFACTURER PART NUMBER") "RC0402FR-074K7L")
        (field (name "TOLERANCE") "1%")
      )
      (libsource (lib "Schlib") (part "RC0402FR-074K7L"))
    )
    (comp (ref "R23")
      (value "5.1k")
      (footprint "RESC1005X37N")
      (fields
        (field (name "MANUFACTURER") "Yageo")
        (field (name "MANUFACTURER PART NUMBER") "AC0402FR-075K1L")
        (field (name "TOLERANCE") "1%")
      )
      (libsource (lib "Schlib") (part "AC0402FR-075K1L"))
    )
    (comp (ref "R24")
      (value "5.1k")
      (footprint "RESC1005X37N")
      (fields
        (field (name "MANUFACTURER") "Yageo")
        (field (name "MANUFACTURER PART NUMBER") "AC0402FR-075K1L")
        (field (name "TOLERANCE") "1%")
      )
      (libsource (lib "Schlib") (part "AC0402FR-075K1L"))
    )
    (comp (ref "R25")
      (value "10k")
      (footprint "RESC1005X40N")
      (description "RES 10K OHM 1% 1/16W 0402")
      (fields
        (field (name "MANUFACTURER") "Yageo")
        (field (name "MANUFACTURER PART NUMBER") "RC0402FR-0710KP")
      )
      (libsource (lib "Schlib_CM5+ESP32") (part "RC0402FR-0710KP"))
    )
    (comp (ref "R26")
      (value "10k")
      (footprint "RESC1005X37N")
      (fields
        (field (name "MANUFACTURER") "Yageo")
        (field (name "MANUFACTURER PART NUMBER") "AC0402FR-0710KL")
        (field (name "TOLERANCE") "1%")
      )
      (libsource (lib "Schlib") (part "AC0402FR-0710KL"))
    )
    (comp (ref "R27")
      (value "10k")
      (footprint "RESC1005X40N")
      (description "RES 10K OHM 1% 1/16W 0402")
      (fields
        (field (name "MANUFACTURER") "Yageo")
        (field (name "MANUFACTURER PART NUMBER") "RC0402FR-0710KP")
      )
      (libsource (lib "Schlib_CM5+ESP32") (part "RC0402FR-0710KP"))
    )
    (comp (ref "R28")
      (value "10k")
      (footprint "RESC1005X40N")
      (description "RES 10K OHM 1% 1/16W 0402")
      (fields
        (field (name "MANUFACTURER") "Yageo")
        (field (name "MANUFACTURER PART NUMBER") "RC0402FR-0710KP")
      )
      (libsource (lib "Schlib_CM5+ESP32") (part "RC0402FR-0710KP"))
    )
    (comp (ref "R29")
      (value "10k")
      (footprint "RESC1005X40N")
      (description "RES 10K OHM 1% 1/16W 0402")
      (fields
        (field (name "MANUFACTURER") "Yageo")
        (field (name "MANUFACTURER PART NUMBER") "RC0402FR-0710KP")
      )
      (libsource (lib "Schlib_CM5+ESP32") (part "RC0402FR-0710KP"))
    )
    (comp (ref "R30")
      (value "10k")
      (footprint "RESC1005X40N")
      (description "RES 10K OHM 1% 1/16W 0402")
      (fields
        (field (name "MANUFACTURER") "Yageo")
        (field (name "MANUFACTURER PART NUMBER") "RC0402FR-0710KP")
      )
      (libsource (lib "Schlib_CM5+ESP32") (part "RC0402FR-0710KP"))
    )
    (comp (ref "R31")
      (value "10k")
      (footprint "RESC1005X40N")
      (description "RES 10K OHM 1% 1/16W 0402")
      (fields
        (field (name "MANUFACTURER") "Yageo")
        (field (name "MANUFACTURER PART NUMBER") "RC0402FR-0710KP")
      )
      (libsource (lib "Schlib_CM5+ESP32") (part "RC0402FR-0710KP"))
    )
    (comp (ref "R32")
      (value "10k")
      (footprint "RESC1005X40N")
      (description "RES 10K OHM 1% 1/16W 0402")
      (fields
        (field (name "MANUFACTURER") "Yageo")
        (field (name "MANUFACTURER PART NUMBER") "RC0402FR-0710KP")
      )
      (libsource (lib "Schlib_CM5+ESP32") (part "RC0402FR-0710KP"))
    )
    (comp (ref "R33")
      (value "10k")
      (footprint "RESC1005X40N")
      (description "RES 10K OHM 1% 1/16W 0402")
      (fields
        (field (name "MANUFACTURER") "Yageo")
        (field (name "MANUFACTURER PART NUMBER") "RC0402FR-0710KP")
      )
      (libsource (lib "Schlib_CM5+ESP32") (part "RC0402FR-0710KP"))
    )
    (comp (ref "R34")
      (value "10k")
      (footprint "RESC1005X40N")
      (description "RES 10K OHM 1% 1/16W 0402")
      (fields
        (field (name "MANUFACTURER") "Yageo")
        (field (name "MANUFACTURER PART NUMBER") "RC0402FR-0710KP")
      )
      (libsource (lib "Schlib_CM5+ESP32") (part "RC0402FR-0710KP"))
    )
    (comp (ref "R35")
      (value "10k")
      (footprint "RESC1005X40N")
      (description "RES 10K OHM 1% 1/16W 0402")
      (fields
        (field (name "MANUFACTURER") "Yageo")
        (field (name "MANUFACTURER PART NUMBER") "RC0402FR-0710KP")
      )
      (libsource (lib "Schlib_CM5+ESP32") (part "RC0402FR-0710KP"))
    )
    (comp (ref "R36")
      (value "10k")
      (footprint "RESC1005X40N")
      (description "RES 10K OHM 1% 1/16W 0402")
      (fields
        (field (name "MANUFACTURER") "Yageo")
        (field (name "MANUFACTURER PART NUMBER") "RC0402FR-0710KP")
      )
      (libsource (lib "Schlib_CM5+ESP32") (part "RC0402FR-0710KP"))
    )
    (comp (ref "R37")
      (value "10k")
      (footprint "RESC1005X40N")
      (description "RES 10K OHM 1% 1/16W 0402")
      (fields
        (field (name "MANUFACTURER") "Yageo")
        (field (name "MANUFACTURER PART NUMBER") "RC0402FR-0710KP")
      )
      (libsource (lib "Schlib_CM5+ESP32") (part "RC0402FR-0710KP"))
    )
    (comp (ref "R38")
      (value "10k")
      (footprint "RESC1005X40N")
      (description "RES 10K OHM 1% 1/16W 0402")
      (fields
        (field (name "MANUFACTURER") "Yageo")
        (field (name "MANUFACTURER PART NUMBER") "RC0402FR-0710KP")
      )
      (libsource (lib "Schlib_CM5+ESP32") (part "RC0402FR-0710KP"))
    )
    (comp (ref "R39")
      (value "10k")
      (footprint "RESC1005X40N")
      (description "RES 10K OHM 1% 1/16W 0402")
      (fields
        (field (name "MANUFACTURER") "Yageo")
        (field (name "MANUFACTURER PART NUMBER") "RC0402FR-0710KP")
      )
      (libsource (lib "Schlib_CM5+ESP32") (part "RC0402FR-0710KP"))
    )
    (comp (ref "R40")
      (value "10k")
      (footprint "RESC1005X40N")
      (description "RES 10K OHM 1% 1/16W 0402")
      (fields
        (field (name "MANUFACTURER") "Yageo")
        (field (name "MANUFACTURER PART NUMBER") "RC0402FR-0710KP")
      )
      (libsource (lib "Schlib_CM5+ESP32") (part "RC0402FR-0710KP"))
    )
    (comp (ref "R41")
      (value "10k")
      (footprint "RESC1005X40N")
      (description "RES 10K OHM 1% 1/16W 0402")
      (fields
        (field (name "MANUFACTURER") "Yageo")
        (field (name "MANUFACTURER PART NUMBER") "RC0402FR-0710KP")
      )
      (libsource (lib "Schlib_CM5+ESP32") (part "RC0402FR-0710KP"))
    )
    (comp (ref "R42")
      (value "10k")
      (footprint "RESC1005X40N")
      (description "RES 10K OHM 1% 1/16W 0402")
      (fields
        (field (name "MANUFACTURER") "Yageo")
        (field (name "MANUFACTURER PART NUMBER") "RC0402FR-0710KP")
      )
      (libsource (lib "Schlib_CM5+ESP32") (part "RC0402FR-0710KP"))
    )
    (comp (ref "R43")
      (value "10k")
      (footprint "RESC1005X40N")
      (description "RES 10K OHM 1% 1/16W 0402")
      (fields
        (field (name "MANUFACTURER") "Yageo")
        (field (name "MANUFACTURER PART NUMBER") "RC0402FR-0710KP")
      )
      (libsource (lib "Schlib_CM5+ESP32") (part "RC0402FR-0710KP"))
    )
    (comp (ref "R44")
      (value "10k")
      (footprint "RESC1005X40N")
      (description "RES 10K OHM 1% 1/16W 0402")
      (fields
        (field (name "MANUFACTURER") "Yageo")
        (field (name "MANUFACTURER PART NUMBER") "RC0402FR-0710KP")
      )
      (libsource (lib "Schlib_CM5+ESP32") (part "RC0402FR-0710KP"))
    )
    (comp (ref "R45")
      (value "510 Ohms, 1/8W")
      (footprint "RESC2012X60N")
      (description "RES 510 OHM 1% 1/8W 0805")
      (fields
        (field (name "MANUFACTURER") "Yageo Group")
        (field (name "MANUFACTURER PART NUMBER") "RC0805FR-07510RL")
      )
      (libsource (lib "Schlib_CM5+ESP32") (part "RC0805FR-07510RL"))
    )
    (comp (ref "R46")
      (value "510 Ohms, 1/8W")
      (footprint "RESC2012X60N")
      (description "RES 510 OHM 1% 1/8W 0805")
      (fields
        (field (name "MANUFACTURER") "Yageo Group")
        (field (name "MANUFACTURER PART NUMBER") "RC0805FR-07510RL")
      )
      (libsource (lib "Schlib_CM5+ESP32") (part "RC0805FR-07510RL"))
    )
    (comp (ref "R47")
      (value "510 Ohms, 1/8W")
      (footprint "RESC2012X60N")
      (description "RES 510 OHM 1% 1/8W 0805")
      (fields
        (field (name "MANUFACTURER") "Yageo Group")
        (field (name "MANUFACTURER PART NUMBER") "RC0805FR-07510RL")
      )
      (libsource (lib "Schlib_CM5+ESP32") (part "RC0805FR-07510RL"))
    )
    (comp (ref "R48")
      (value "510 Ohms, 1/8W")
      (footprint "RESC2012X60N")
      (description "RES 510 OHM 1% 1/8W 0805")
      (fields
        (field (name "MANUFACTURER") "Yageo Group")
        (field (name "MANUFACTURER PART NUMBER") "RC0805FR-07510RL")
      )
      (libsource (lib "Schlib_CM5+ESP32") (part "RC0805FR-07510RL"))
    )
    (comp (ref "R49")
      (value "510 Ohms, 1/8W")
      (footprint "RESC2012X60N")
      (description "RES 510 OHM 1% 1/8W 0805")
      (fields
        (field (name "MANUFACTURER") "Yageo Group")
        (field (name "MANUFACTURER PART NUMBER") "RC0805FR-07510RL")
      )
      (libsource (lib "Schlib_CM5+ESP32") (part "RC0805FR-07510RL"))
    )
    (comp (ref "R50")
      (value "510 Ohms, 1/8W")
      (footprint "RESC2012X60N")
      (description "RES 510 OHM 1% 1/8W 0805")
      (fields
        (field (name "MANUFACTURER") "Yageo Group")
        (field (name "MANUFACTURER PART NUMBER") "RC0805FR-07510RL")
      )
      (libsource (lib "Schlib_CM5+ESP32") (part "RC0805FR-07510RL"))
    )
    (comp (ref "R51")
      (value "10k")
      (footprint "RESC1005X40N")
      (description "RES 10K OHM 1% 1/16W 0402")
      (fields
        (field (name "MANUFACTURER") "Yageo")
        (field (name "MANUFACTURER PART NUMBER") "RC0402FR-0710KP")
      )
      (libsource (lib "Schlib_CM5+ESP32") (part "RC0402FR-0710KP"))
    )
    (comp (ref "R52")
      (value "10k")
      (footprint "RESC1005X40N")
      (description "RES 10K OHM 1% 1/16W 0402")
      (fields
        (field (name "MANUFACTURER") "Yageo")
        (field (name "MANUFACTURER PART NUMBER") "RC0402FR-0710KP")
      )
      (libsource (lib "Schlib_CM5+ESP32") (part "RC0402FR-0710KP"))
    )
    (comp (ref "R53")
      (value "10k")
      (footprint "RESC1005X40N")
      (description "RES 10K OHM 1% 1/16W 0402")
      (fields
        (field (name "MANUFACTURER") "Yageo")
        (field (name "MANUFACTURER PART NUMBER") "RC0402FR-0710KP")
      )
      (libsource (lib "Schlib_CM5+ESP32") (part "RC0402FR-0710KP"))
    )
    (comp (ref "R54")
      (value "10k")
      (footprint "RESC1005X40N")
      (description "RES 10K OHM 1% 1/16W 0402")
      (fields
        (field (name "MANUFACTURER") "Yageo")
        (field (name "MANUFACTURER PART NUMBER") "RC0402FR-0710KP")
      )
      (libsource (lib "Schlib_CM5+ESP32") (part "RC0402FR-0710KP"))
    )
    (comp (ref "R55")
      (value "10k")
      (footprint "RESC1005X40N")
      (description "RES 10K OHM 1% 1/16W 0402")
      (fields
        (field (name "MANUFACTURER") "Yageo")
        (field (name "MANUFACTURER PART NUMBER") "RC0402FR-0710KP")
      )
      (libsource (lib "Schlib_CM5+ESP32") (part "RC0402FR-0710KP"))
    )
    (comp (ref "R56")
      (value "10k")
      (footprint "RESC1005X40N")
      (description "RES 10K OHM 1% 1/16W 0402")
      (fields
        (field (name "MANUFACTURER") "Yageo")
        (field (name "MANUFACTURER PART NUMBER") "RC0402FR-0710KP")
      )
      (libsource (lib "Schlib_CM5+ESP32") (part "RC0402FR-0710KP"))
    )
    (comp (ref "R57")
      (value "10kOhm")
      (footprint "RESC0603X26N - duplicate")
      (description "RES 10K OHM 1% 1/20W 0201")
      (fields
        (field (name "MANUFACTURER") "Yageo")
        (field (name "MANUFACTURER PART NUMBER") "RC0201FR-0710KL")
      )
      (libsource (lib "Schlib_CM5+ESP32") (part "RC0201FR-0710KL"))
    )
    (comp (ref "R58")
      (value "27R")
      (footprint "RESC1005X37N")
      (fields
        (field (name "MANUFACTURER") "Yageo")
        (field (name "MANUFACTURER PART NUMBER") "RC0402FR-0727RL")
        (field (name "TOLERANCE") "1%")
      )
      (libsource (lib "Schlib") (part "RC0402FR-0727RL"))
    )
    (comp (ref "R59")
      (value "27R")
      (footprint "RESC1005X37N")
      (fields
        (field (name "MANUFACTURER") "Yageo")
        (field (name "MANUFACTURER PART NUMBER") "RC0402FR-0727RL")
        (field (name "TOLERANCE") "1%")
      )
      (libsource (lib "Schlib") (part "RC0402FR-0727RL"))
    )
    (comp (ref "SW2")
      (value "PTS645SH50SMTR92LFS")
      (footprint "FP-PTS645SH50SMTR92LFS-MFG")
      (fields (field (name "MANUFACTURER") "ITT C&K") (field (name "LCSC PART NUMBER") "C221869"))
      (libsource (lib "Schlib") (part "PTS645SH50SMTR92LFS"))
    )
    (comp (ref "SW3")
      (value "PTS645SH50SMTR92LFS")
      (footprint "FP-PTS645SH50SMTR92LFS-MFG")
      (fields (field (name "MANUFACTURER") "ITT C&K") (field (name "LCSC PART NUMBER") "C221869"))
      (libsource (lib "Schlib") (part "PTS645SH50SMTR92LFS"))
    )
    (comp (ref "U1")
      (value "TPS563209DDCR")
      (footprint "DDC0006A")
      (description "IC REG BUCK ADJ 3A SOT23")
      (fields (field (name "MANUFACTURER") "Texas Instruments") (field (name "LCSC PART NUMBER") "C181974"))
      (libsource (lib "Schlib_CM5+ESP32") (part "TPS563209DDCR"))
    )
    (comp (ref "U3")
      (value "TL1963A-33DCYR")
      (footprint "DCY0004A_N")
      (description "Fixed Positive LDO Regulator, 3.3V, 0.55V Dropout, BIPolar, PDSO4")
      (fields (field (name "MANUFACTURER") "Texas Instruments") (field (name "LCSC PART NUMBER") "C181262"))
      (libsource (lib "Schlib_PersonalProject") (part "TL1963A-33DCYR"))
    )
    (comp (ref "U4")
      (value "FT231XQ-R")
      (footprint "FP-QFN-20-IPC_B")
      (description "IC USB SERIAL FULL UART 20QFN")
      (fields (field (name "MANUFACTURER") "FTDI") (field (name "LCSC PART NUMBER") "C132159"))
      (libsource (lib "Schlib") (part "FT231XQ-R"))
    )
    (comp (ref "U7")
      (value "AND Gate")
      (footprint "SOT95P280X145-5N")
      (description "IC GATE AND 1CH 2-INP SOT23-5")
      (fields
        (field (name "MANUFACTURER") "Texas Instruments")
        (field (name "MANUFACTURER PART NUMBER") "SN74LVC1G08DBVR")
      )
      (libsource (lib "Schlib_CM5+ESP32") (part "SN74LVC1G08DBVR"))
    )
    (comp (ref "U8")
      (value "AND Gate")
      (footprint "SOT95P280X145-5N")
      (description "IC GATE AND 1CH 2-INP SOT23-5")
      (fields
        (field (name "MANUFACTURER") "Texas Instruments")
        (field (name "MANUFACTURER PART NUMBER") "SN74LVC1G08DBVR")
      )
      (libsource (lib "Schlib_CM5+ESP32") (part "SN74LVC1G08DBVR"))
    )
    (comp (ref "U9")
      (value "AND Gate")
      (footprint "SOT95P280X145-5N")
      (description "IC GATE AND 1CH 2-INP SOT23-5")
      (fields
        (field (name "MANUFACTURER") "Texas Instruments")
        (field (name "MANUFACTURER PART NUMBER") "SN74LVC1G08DBVR")
      )
      (libsource (lib "Schlib_CM5+ESP32") (part "SN74LVC1G08DBVR"))
    )
    (comp (ref "U10")
      (value "AND Gate")
      (footprint "SOT95P280X145-5N")
      (description "IC GATE AND 1CH 2-INP SOT23-5")
      (fields
        (field (name "MANUFACTURER") "Texas Instruments")
        (field (name "MANUFACTURER PART NUMBER") "SN74LVC1G08DBVR")
      )
      (libsource (lib "Schlib_CM5+ESP32") (part "SN74LVC1G08DBVR"))
    )
    (comp (ref "U11")
      (value "AND Gate")
      (footprint "SOT95P280X145-5N")
      (description "IC GATE AND 1CH 2-INP SOT23-5")
      (fields
        (field (name "MANUFACTURER") "Texas Instruments")
        (field (name "MANUFACTURER PART NUMBER") "SN74LVC1G08DBVR")
      )
      (libsource (lib "Schlib_CM5+ESP32") (part "SN74LVC1G08DBVR"))
    )
    (comp (ref "U12")
      (value "AND Gate")
      (footprint "SOT95P280X145-5N")
      (description "IC GATE AND 1CH 2-INP SOT23-5")
      (fields
        (field (name "MANUFACTURER") "Texas Instruments")
        (field (name "MANUFACTURER PART NUMBER") "SN74LVC1G08DBVR")
      )
      (libsource (lib "Schlib_CM5+ESP32") (part "SN74LVC1G08DBVR"))
    )
    (comp (ref "U13")
      (value "INVERTER")
      (footprint "SOT95P280X145-5N")
      (description "Inverter IC 1 Channel Schmitt Trigger SOT-23-5")
      (fields
        (field (name "MANUFACTURER") "Texas Instruments")
        (field (name "MANUFACTURER PART NUMBER") "SN74AHC1G14DBVR")
      )
      (libsource (lib "Schlib_CM5+ESP32") (part "SN74AHC1G14DBVR"))
    )
    (comp (ref "U14")
      (value "INVERTER")
      (footprint "SOT95P280X145-5N")
      (description "Inverter IC 1 Channel Schmitt Trigger SOT-23-5")
      (fields
        (field (name "MANUFACTURER") "Texas Instruments")
        (field (name "MANUFACTURER PART NUMBER") "SN74AHC1G14DBVR")
      )
      (libsource (lib "Schlib_CM5+ESP32") (part "SN74AHC1G14DBVR"))
    )
    (comp (ref "U15")
      (value "INVERTER")
      (footprint "SOT95P280X145-5N")
      (description "Inverter IC 1 Channel Schmitt Trigger SOT-23-5")
      (fields
        (field (name "MANUFACTURER") "Texas Instruments")
        (field (name "MANUFACTURER PART NUMBER") "SN74AHC1G14DBVR")
      )
      (libsource (lib "Schlib_CM5+ESP32") (part "SN74AHC1G14DBVR"))
    )
    (comp (ref "U16")
      (value "BTN8982TA")
      (footprint "IC8_BTN8982TAAUMA1_INF")
      (description "Half Bridge Driver DC Motors, General Purpose DMOS PG-TO263-7-1")
      (fields
        (field (name "MANUFACTURER") "Infineon")
        (field (name "MANUFACTURER PART NUMBER") "BTN8982TAAUMA1")
      )
      (libsource (lib "Schlib_CM5+ESP32") (part "BTN8982TAAUMA1"))
    )
    (comp (ref "U17")
      (value "BTN8982TA")
      (footprint "IC8_BTN8982TAAUMA1_INF")
      (description "Half Bridge Driver DC Motors, General Purpose DMOS PG-TO263-7-1")
      (fields
        (field (name "MANUFACTURER") "Infineon")
        (field (name "MANUFACTURER PART NUMBER") "BTN8982TAAUMA1")
      )
      (libsource (lib "Schlib_CM5+ESP32") (part "BTN8982TAAUMA1"))
    )
    (comp (ref "U18")
      (value "BTN8982TA")
      (footprint "IC8_BTN8982TAAUMA1_INF")
      (description "Half Bridge Driver DC Motors, General Purpose DMOS PG-TO263-7-1")
      (fields
        (field (name "MANUFACTURER") "Infineon")
        (field (name "MANUFACTURER PART NUMBER") "BTN8982TAAUMA1")
      )
      (libsource (lib "Schlib_CM5+ESP32") (part "BTN8982TAAUMA1"))
    )
    (comp (ref "U19")
      (value "BTN8982TA")
      (footprint "IC8_BTN8982TAAUMA1_INF")
      (description "Half Bridge Driver DC Motors, General Purpose DMOS PG-TO263-7-1")
      (fields
        (field (name "MANUFACTURER") "Infineon")
        (field (name "MANUFACTURER PART NUMBER") "BTN8982TAAUMA1")
      )
      (libsource (lib "Schlib_CM5+ESP32") (part "BTN8982TAAUMA1"))
    )
    (comp (ref "U20")
      (value "BTN8982TA")
      (footprint "IC8_BTN8982TAAUMA1_INF")
      (description "Half Bridge Driver DC Motors, General Purpose DMOS PG-TO263-7-1")
      (fields
        (field (name "MANUFACTURER") "Infineon")
        (field (name "MANUFACTURER PART NUMBER") "BTN8982TAAUMA1")
      )
      (libsource (lib "Schlib_CM5+ESP32") (part "BTN8982TAAUMA1"))
    )
    (comp (ref "U21")
      (value "BTN8982TA")
      (footprint "IC8_BTN8982TAAUMA1_INF")
      (description "Half Bridge Driver DC Motors, General Purpose DMOS PG-TO263-7-1")
      (fields
        (field (name "MANUFACTURER") "Infineon")
        (field (name "MANUFACTURER PART NUMBER") "BTN8982TAAUMA1")
      )
      (libsource (lib "Schlib_CM5+ESP32") (part "BTN8982TAAUMA1"))
    )
    (comp (ref "U24")
      (value "IPD90P03P4L04ATMA2")
      (footprint "TO228P998X235-3N-2-V")
      (description "MOSFET P-CH 30V 90A TO252-31 P-Channel 30 V 90A (Tc) 137W (Tc) Surface Mount PG-TO252-3-11")
      (fields (field (name "MANUFACTURER") "Infineon") (field (name "LCSC PART NUMBER") "C148284"))
      (libsource (lib "Schlib_CM5+ESP32") (part "IPD90P03P4L04ATMA2"))
    )
    (comp (ref "U25")
      (value "RA-02")
      (footprint "MODULE_RA-02_LORA")
      (description "RF TXRX MOD ISM<1GHZIPEX SMD")
      (fields (field (name "MANUFACTURER") "Ai-Thinker") (field (name "LCSC PART NUMBER") "C90039"))
      (libsource (lib "Schlib_CM5+ESP32") (part "RA-02"))
    )
  )
  (nets
    (net (code "1") (name "+3V3") (class "Default")
      (node (ref "C1") (pin "2") (pinfunction "2_2") (pintype "passive"))
      (node (ref "C15") (pin "2") (pinfunction "2_2") (pintype "passive"))
      (node (ref "C16") (pin "2") (pinfunction "2_2") (pintype "passive"))
      (node (ref "C2") (pin "2") (pinfunction "2_2") (pintype "passive"))
      (node (ref "C24") (pin "2") (pinfunction "2_2") (pintype "passive"))
      (node (ref "C25") (pin "2") (pinfunction "2_2") (pintype "passive"))
      (node (ref "C26") (pin "2") (pinfunction "2_2") (pintype "passive"))
      (node (ref "C27") (pin "2") (pinfunction "2_2") (pintype "passive"))
      (node (ref "C28") (pin "2") (pinfunction "2_2") (pintype "passive"))
      (node (ref "C29") (pin "2") (pinfunction "2_2") (pintype "passive"))
      (node (ref "C30") (pin "2") (pinfunction "2_2") (pintype "passive"))
      (node (ref "C31") (pin "2") (pinfunction "2_2") (pintype "passive"))
      (node (ref "C32") (pin "2") (pinfunction "2_2") (pintype "passive"))
      (node (ref "C60") (pin "2") (pinfunction "2_2") (pintype "passive"))
      (node (ref "C61") (pin "2") (pinfunction "2_2") (pintype "passive"))
      (node (ref "ESP32-S3-WROOM-1U-N16R8") (pin "2") (pinfunction "3V3_2") (pintype "power_in"))
      (node (ref "FB1") (pin "2") (pinfunction "2_2") (pintype "passive"))
      (node (ref "J3") (pin "2") (pinfunction "2_2") (pintype "passive"))
      (node (ref "J4") (pin "2") (pinfunction "2_2") (pintype "passive"))
      (node (ref "J5") (pin "2") (pinfunction "2_2") (pintype "passive"))
      (node (ref "R1") (pin "2") (pinfunction "2_2") (pintype "passive"))
      (node (ref "R11") (pin "2") (pinfunction "2_2") (pintype "passive"))
      (node (ref "R2") (pin "2") (pinfunction "2_2") (pintype "passive"))
      (node (ref "R3") (pin "2") (pinfunction "2_2") (pintype "passive"))
      (node (ref "R51") (pin "1") (pinfunction "1_1") (pintype "passive"))
      (node (ref "R52") (pin "1") (pinfunction "1_1") (pintype "passive"))
      (node (ref "R53") (pin "1") (pinfunction "1_1") (pintype "passive"))
      (node (ref "R54") (pin "1") (pinfunction "1_1") (pintype "passive"))
      (node (ref "R55") (pin "1") (pinfunction "1_1") (pintype "passive"))
      (node (ref "R56") (pin "1") (pinfunction "1_1") (pintype "passive"))
      (node (ref "R57") (pin "2") (pinfunction "2_2") (pintype "passive"))
      (node (ref "U10") (pin "5") (pinfunction "VCC_5") (pintype "power_in"))
      (node (ref "U11") (pin "5") (pinfunction "VCC_5") (pintype "power_in"))
      (node (ref "U12") (pin "5") (pinfunction "VCC_5") (pintype "power_in"))
      (node (ref "U13") (pin "5") (pinfunction "VCC_5") (pintype "power_in"))
      (node (ref "U14") (pin "5") (pinfunction "VCC_5") (pintype "power_in"))
      (node (ref "U15") (pin "5") (pinfunction "VCC_5") (pintype "power_in"))
      (node (ref "U25") (pin "3") (pinfunction "3V3_3") (pintype "passive"))
      (node (ref "U3") (pin "3") (pinfunction "OUT_3") (pintype "power_in"))
      (node (ref "U7") (pin "5") (pinfunction "VCC_5") (pintype "power_in"))
      (node (ref "U8") (pin "5") (pinfunction "VCC_5") (pintype "power_in"))
      (node (ref "U9") (pin "5") (pinfunction "VCC_5") (pintype "power_in"))
    )
    (net (code "2") (name "+5V") (class "Default")
      (node (ref "C6") (pin "2") (pinfunction "2_2") (pintype "passive"))
      (node (ref "J14") (pin "2") (pinfunction "2_2") (pintype "passive"))
      (node (ref "U3") (pin "1") (pinfunction "IN_1") (pintype "power_in"))
    )
    (net (code "3") (name "+5V_VBUS") (class "Default")
      (node (ref "C21") (pin "2") (pinfunction "2_2") (pintype "passive"))
      (node (ref "D10") (pin "2") (pinfunction "2_2") (pintype "passive"))
      (node (ref "J14") (pin "1") (pinfunction "1_1") (pintype "passive"))
      (node (ref "J18") (pin "A4B9") (pinfunction "VBUS_A4B9_A4B9") (pintype "passive"))
      (node (ref "J18") (pin "B4A9") (pinfunction "VBUS_B4A9_B4A9") (pintype "passive"))
      (node (ref "R17") (pin "1") (pinfunction "1_1") (pintype "passive"))
      (node (ref "R22") (pin "2") (pinfunction "2_2") (pintype "passive"))
    )
    (net (code "4") (name "/+3V3_FTDI") (class "Default")
      (node (ref "C22") (pin "2") (pinfunction "2_2") (pintype "passive"))
      (node (ref "C23") (pin "2") (pinfunction "2_2") (pintype "passive"))
      (node (ref "R21") (pin "1") (pinfunction "1_1") (pintype "passive"))
      (node (ref "U4") (pin "10") (pinfunction "3V3OUT_10") (pintype "passive"))
      (node (ref "U4") (pin "20") (pinfunction "VCCIO_20") (pintype "passive"))
    )
    (net (code "5") (name "/+VCC_FTDI") (class "Default")
      (node (ref "C19") (pin "2") (pinfunction "2_2") (pintype "passive"))
      (node (ref "C20") (pin "2") (pinfunction "2_2") (pintype "passive"))
      (node (ref "R17") (pin "2") (pinfunction "2_2") (pintype "passive"))
      (node (ref "U4") (pin "12") (pinfunction "VCC_12") (pintype "passive"))
    )
    (net (code "6") (name "/BTN GPI0") (class "Default")
      (node (ref "C4") (pin "2") (pinfunction "2_2") (pintype "passive"))
      (node (ref "Q2") (pin "3") (pinfunction "C_3") (pintype "passive"))
      (node (ref "R12") (pin "2") (pinfunction "2_2") (pintype "passive"))
      (node (ref "SW3") (pin "1") (pinfunction "1_1") (pintype "passive"))
      (node (ref "SW3") (pin "2") (pinfunction "2_2") (pintype "passive"))
    )
    (net (code "7") (name "/CHIP_PU") (class "Default")
      (node (ref "C3") (pin "2") (pinfunction "2_2") (pintype "passive"))
      (node (ref "ESP32-S3-WROOM-1U-N16R8") (pin "3") (pinfunction "EN_3") (pintype "passive"))
      (node (ref "Q1") (pin "3") (pinfunction "C_3") (pintype "passive"))
      (node (ref "R1") (pin "1") (pinfunction "1_1") (pintype "passive"))
      (node (ref "SW2") (pin "1") (pinfunction "1_1") (pintype "passive"))
      (node (ref "SW2") (pin "2") (pinfunction "2_2") (pintype "passive"))
    )
    (net (code "8") (name "/CON1_USB_N") (class "Default")
      (node (ref "D11") (pin "2") (pinfunction "2_2") (pintype "passive"))
      (node (ref "J18") (pin "A7") (pinfunction "DN1_A7") (pintype "passive"))
      (node (ref "J18") (pin "B7") (pinfunction "DN2_B7") (pintype "passive"))
      (node (ref "R19") (pin "2") (pinfunction "2_2") (pintype "passive"))
    )
    (net (code "9") (name "/CON1_USB_P") (class "Default")
      (node (ref "D12") (pin "2") (pinfunction "2_2") (pintype "passive"))
      (node (ref "J18") (pin "A6") (pinfunction "DP1_A6") (pintype "passive"))
      (node (ref "J18") (pin "B6") (pinfunction "DP2_B6") (pintype "passive"))
      (node (ref "R20") (pin "2") (pinfunction "2_2") (pintype "passive"))
    )
    (net (code "10") (name "/CS_Main") (class "Default")
      (node (ref "ESP32-S3-WROOM-1U-N16R8") (pin "31") (pinfunction "IO38_31") (pintype "passive"))
      (node (ref "R57") (pin "1") (pinfunction "1_1") (pintype "passive"))
    )
    (net (code "11") (name "/DTR_FTDI") (class "Default")
      (node (ref "Q2") (pin "2") (pinfunction "E_2") (pintype "passive"))
      (node (ref "R13") (pin "2") (pinfunction "2_2") (pintype "passive"))
      (node (ref "U4") (pin "18") (pinfunction "~{DTR}_18") (pintype "passive"))
    )
    (net (code "12") (name "/ESP_GPIO1") (class "Default")
      (node (ref "ESP32-S3-WROOM-1U-N16R8") (pin "39") (pinfunction "IO1_39") (pintype "passive"))
      (node (ref "U25") (pin "4") (pinfunction "RESET_4") (pintype "passive"))
    )
    (net (code "13") (name "/ESP_GPIO2") (class "Default")
      (node (ref "D7") (pin "1") (pinfunction "1_1") (pintype "passive"))
      (node (ref "ESP32-S3-WROOM-1U-N16R8") (pin "38") (pinfunction "IO2_38") (pintype "passive"))
      (node (ref "U25") (pin "5") (pinfunction "DIO0_5") (pintype "passive"))
    )
    (net (code "14") (name "/ESP_GPIO3") (class "Default")
      (node (ref "ESP32-S3-WROOM-1U-N16R8") (pin "15") (pinfunction "IO3_15") (pintype "passive"))
      (node (ref "J7") (pin "2") (pinfunction "2_2") (pintype "passive"))
      (node (ref "R32") (pin "2") (pinfunction "2_2") (pintype "passive"))
      (node (ref "R37") (pin "2") (pinfunction "2_2") (pintype "passive"))
      (node (ref "U11") (pin "1") (pinfunction "A_1") (pintype "passive"))
      (node (ref "U12") (pin "1") (pinfunction "A_1") (pintype "passive"))
    )
    (net (code "15") (name "/ESP_GPIO4") (class "Default")
      (node (ref "ESP32-S3-WROOM-1U-N16R8") (pin "4") (pinfunction "IO4_4") (pintype "passive"))
      (node (ref "J3") (pin "4") (pinfunction "4_4") (pintype "passive"))
    )
    (net (code "16") (name "/ESP_GPIO5") (class "Default")
      (node (ref "ESP32-S3-WROOM-1U-N16R8") (pin "5") (pinfunction "IO5_5") (pintype "passive"))
      (node (ref "J3") (pin "3") (pinfunction "3_3") (pintype "passive"))
    )
    (net (code "17") (name "/ESP_GPIO6") (class "Default")
      (node (ref "ESP32-S3-WROOM-1U-N16R8") (pin "6") (pinfunction "IO6_6") (pintype "passive"))
      (node (ref "J7") (pin "1") (pinfunction "1_1") (pintype "passive"))
      (node (ref "R29") (pin "2") (pinfunction "2_2") (pintype "passive"))
      (node (ref "R38") (pin "2") (pinfunction "2_2") (pintype "passive"))
      (node (ref "U11") (pin "2") (pinfunction "B_2") (pintype "passive"))
      (node (ref "U15") (pin "2") (pinfunction "A_2") (pintype "passive"))
    )
    (net (code "18") (name "/ESP_GPIO7") (class "Default")
      (node (ref "ESP32-S3-WROOM-1U-N16R8") (pin "7") (pinfunction "IO7_7") (pintype "passive"))
      (node (ref "J7") (pin "3") (pinfunction "3_3") (pintype "passive"))
    )
    (net (code "19") (name "/ESP_GPIO8") (class "Default")
      (node (ref "ESP32-S3-WROOM-1U-N16R8") (pin "12") (pinfunction "IO8_12") (pintype "passive"))
      (node (ref "J4") (pin "3") (pinfunction "3_3") (pintype "passive"))
      (node (ref "J5") (pin "3") (pinfunction "3_3") (pintype "passive"))
    )
    (net (code "20") (name "/ESP_GPIO9") (class "Default")
      (node (ref "ESP32-S3-WROOM-1U-N16R8") (pin "17") (pinfunction "IO9_17") (pintype "passive"))
      (node (ref "J4") (pin "4") (pinfunction "4_4") (pintype "passive"))
      (node (ref "J5") (pin "4") (pinfunction "4_4") (pintype "passive"))
    )
    (net (code "21") (name "/ESP_GPIO10") (class "Default")
      (node (ref "ESP32-S3-WROOM-1U-N16R8") (pin "18") (pinfunction "IO10_18") (pintype "passive"))
      (node (ref "J7") (pin "4") (pinfunction "4_4") (pintype "passive"))
    )
    (net (code "22") (name "/ESP_GPIO11") (class "Default")
      (node (ref "R58") (pin "1") (pinfunction "1_1") (pintype "passive"))
      (node (ref "U25") (pin "14") (pinfunction "MOSI_14") (pintype "passive"))
    )
    (net (code "23") (name "/ESP_GPIO12") (class "Default")
      (node (ref "R59") (pin "1") (pinfunction "1_1") (pintype "passive"))
      (node (ref "U25") (pin "12") (pinfunction "SCK_12") (pintype "passive"))
    )
    (net (code "24") (name "/ESP_GPIO13") (class "Default")
      (node (ref "ESP32-S3-WROOM-1U-N16R8") (pin "21") (pinfunction "IO13_21") (pintype "passive"))
      (node (ref "R15") (pin "2") (pinfunction "2_2") (pintype "passive"))
    )
    (net (code "25") (name "/ESP_GPIO14") (class "Default")
      (node (ref "ESP32-S3-WROOM-1U-N16R8") (pin "22") (pinfunction "IO14_22") (pintype "passive"))
      (node (ref "R11") (pin "1") (pinfunction "1_1") (pintype "passive"))
      (node (ref "U25") (pin "15") (pinfunction "NSS_15") (pintype "passive"))
    )
    (net (code "26") (name "/ESP_GPIO15") (class "Default")
      (node (ref "ESP32-S3-WROOM-1U-N16R8") (pin "8") (pinfunction "IO15_8") (pintype "passive"))
      (node (ref "J6") (pin "1") (pinfunction "1_1") (pintype "passive"))
      (node (ref "R27") (pin "2") (pinfunction "2_2") (pintype "passive"))
      (node (ref "R34") (pin "2") (pinfunction "2_2") (pintype "passive"))
      (node (ref "U13") (pin "2") (pinfunction "A_2") (pintype "passive"))
      (node (ref "U7") (pin "2") (pinfunction "B_2") (pintype "passive"))
    )
    (net (code "27") (name "/ESP_GPIO16") (class "Default")
      (node (ref "ESP32-S3-WROOM-1U-N16R8") (pin "9") (pinfunction "IO16_9") (pintype "passive"))
      (node (ref "J6") (pin "2") (pinfunction "2_2") (pintype "passive"))
      (node (ref "R30") (pin "2") (pinfunction "2_2") (pintype "passive"))
      (node (ref "R33") (pin "2") (pinfunction "2_2") (pintype "passive"))
      (node (ref "U7") (pin "1") (pinfunction "A_1") (pintype "passive"))
      (node (ref "U8") (pin "1") (pinfunction "A_1") (pintype "passive"))
    )
    (net (code "28") (name "/ESP_GPIO17") (class "Default")
      (node (ref "ESP32-S3-WROOM-1U-N16R8") (pin "10") (pinfunction "IO17_10") (pintype "passive"))
      (node (ref "J6") (pin "3") (pinfunction "3_3") (pintype "passive"))
      (node (ref "R28") (pin "2") (pinfunction "2_2") (pintype "passive"))
      (node (ref "R36") (pin "2") (pinfunction "2_2") (pintype "passive"))
      (node (ref "U14") (pin "2") (pinfunction "A_2") (pintype "passive"))
      (node (ref "U9") (pin "2") (pinfunction "B_2") (pintype "passive"))
    )
    (net (code "29") (name "/ESP_GPIO18") (class "Default")
      (node (ref "ESP32-S3-WROOM-1U-N16R8") (pin "11") (pinfunction "IO18_11") (pintype "passive"))
      (node (ref "J6") (pin "4") (pinfunction "4_4") (pintype "passive"))
      (node (ref "R31") (pin "2") (pinfunction "2_2") (pintype "passive"))
      (node (ref "R35") (pin "2") (pinfunction "2_2") (pintype "passive"))
      (node (ref "U10") (pin "1") (pinfunction "A_1") (pintype "passive"))
      (node (ref "U9") (pin "1") (pinfunction "A_1") (pintype "passive"))
    )
    (net (code "30") (name "/ESP_GPIO47") (class "Default")
      (node (ref "ESP32-S3-WROOM-1U-N16R8") (pin "24") (pinfunction "IO47_24") (pintype "passive"))
      (node (ref "J8") (pin "1") (pinfunction "1_1") (pintype "passive"))
    )
    (net (code "31") (name "/ESP_GPIO48") (class "Default")
      (node (ref "ESP32-S3-WROOM-1U-N16R8") (pin "25") (pinfunction "IO48_25") (pintype "passive"))
      (node (ref "J8") (pin "2") (pinfunction "2_2") (pintype "passive"))
    )
    (net (code "32") (name "/FTDI_RESET") (class "Default")
      (node (ref "R21") (pin "2") (pinfunction "2_2") (pintype "passive"))
      (node (ref "U4") (pin "11") (pinfunction "~{RESET}_11") (pintype "passive"))
    )
    (net (code "33") (name "/FTDI_USB_N") (class "Default")
      (node (ref "R19") (pin "1") (pinfunction "1_1") (pintype "passive"))
      (node (ref "U4") (pin "9") (pinfunction "USBDM_9") (pintype "passive"))
    )
    (net (code "34") (name "/FTDI_USB_P") (class "Default")
      (node (ref "R20") (pin "1") (pinfunction "1_1") (pintype "passive"))
      (node (ref "U4") (pin "8") (pinfunction "USBDP_8") (pintype "passive"))
    )
    (net (code "35") (name "/M1+") (class "Default")
      (node (ref "U16") (pin "2") (pinfunction "IN_2") (pintype "passive"))
      (node (ref "U7") (pin "4") (pinfunction "Y_4") (pintype "passive"))
    )
    (net (code "36") (name "/M1-") (class "Default")
      (node (ref "U17") (pin "2") (pinfunction "IN_2") (pintype "passive"))
      (node (ref "U8") (pin "4") (pinfunction "Y_4") (pintype "passive"))
    )
    (net (code "37") (name "/M2+") (class "Default")
      (node (ref "U18") (pin "2") (pinfunction "IN_2") (pintype "passive"))
      (node (ref "U9") (pin "4") (pinfunction "Y_4") (pintype "passive"))
    )
    (net (code "38") (name "/M2-") (class "Default")
      (node (ref "U10") (pin "4") (pinfunction "Y_4") (pintype "passive"))
      (node (ref "U19") (pin "2") (pinfunction "IN_2") (pintype "passive"))
    )
    (net (code "39") (name "/M3+") (class "Default")
      (node (ref "U11") (pin "4") (pinfunction "Y_4") (pintype "passive"))
      (node (ref "U20") (pin "2") (pinfunction "IN_2") (pintype "passive"))
    )
    (net (code "40") (name "/M3-") (class "Default")
      (node (ref "U12") (pin "4") (pinfunction "Y_4") (pintype "passive"))
      (node (ref "U21") (pin "2") (pinfunction "IN_2") (pintype "passive"))
    )
    (net (code "41") (name "/MISO_Main") (class "Default")
      (node (ref "R16") (pin "2") (pinfunction "2_2") (pintype "passive"))
    )
    (net (code "42") (name "/MOSI_Main") (class "Default")
      (node (ref "ESP32-S3-WROOM-1U-N16R8") (pin "28") (pinfunction "IO35_28") (pintype "passive"))
    )
    (net (code "43") (name "/MOTOR1+") (class "Default")
      (node (ref "C40") (pin "2") (pinfunction "2_2") (pintype "passive"))
      (node (ref "C42") (pin "2") (pinfunction "2_2") (pintype "passive"))
      (node (ref "J10") (pin "1") (pinfunction "1_1") (pintype "passive"))
      (node (ref "J19") (pin "2") (pinfunction "2_2") (pintype "passive"))
      (node (ref "U16") (pin "4") (pinfunction "OUT_4") (pintype "passive"))
      (node (ref "U16") (pin "8") (pinfunction "OUT_8") (pintype "passive"))
    )
    (net (code "44") (name "/MOTOR1-") (class "Default")
      (node (ref "C41") (pin "2") (pinfunction "2_2") (pintype "passive"))
      (node (ref "C43") (pin "2") (pinfunction "2_2") (pintype "passive"))
      (node (ref "J10") (pin "2") (pinfunction "2_2") (pintype "passive"))
      (node (ref "J19") (pin "1") (pinfunction "1_1") (pintype "passive"))
      (node (ref "U17") (pin "4") (pinfunction "OUT_4") (pintype "passive"))
      (node (ref "U17") (pin "8") (pinfunction "OUT_8") (pintype "passive"))
    )
    (net (code "45") (name "/MOTOR2+") (class "Default")
      (node (ref "C46") (pin "2") (pinfunction "2_2") (pintype "passive"))
      (node (ref "C48") (pin "2") (pinfunction "2_2") (pintype "passive"))
      (node (ref "J20") (pin "2") (pinfunction "2_2") (pintype "passive"))
      (node (ref "J23") (pin "1") (pinfunction "1_1") (pintype "passive"))
      (node (ref "U18") (pin "4") (pinfunction "OUT_4") (pintype "passive"))
      (node (ref "U18") (pin "8") (pinfunction "OUT_8") (pintype "passive"))
    )
    (net (code "46") (name "/MOTOR2-") (class "Default")
      (node (ref "C47") (pin "2") (pinfunction "2_2") (pintype "passive"))
      (node (ref "C49") (pin "2") (pinfunction "2_2") (pintype "passive"))
      (node (ref "J20") (pin "1") (pinfunction "1_1") (pintype "passive"))
      (node (ref "J23") (pin "2") (pinfunction "2_2") (pintype "passive"))
      (node (ref "U19") (pin "4") (pinfunction "OUT_4") (pintype "passive"))
      (node (ref "U19") (pin "8") (pinfunction "OUT_8") (pintype "passive"))
    )
    (net (code "47") (name "/MOTOR3+") (class "Default")
      (node (ref "C50") (pin "2") (pinfunction "2_2") (pintype "passive"))
      (node (ref "C52") (pin "2") (pinfunction "2_2") (pintype "passive"))
      (node (ref "J22") (pin "2") (pinfunction "2_2") (pintype "passive"))
      (node (ref "U20") (pin "4") (pinfunction "OUT_4") (pintype "passive"))
      (node (ref "U20") (pin "8") (pinfunction "OUT_8") (pintype "passive"))
    )
    (net (code "48") (name "/MOTOR3-") (class "Default")
      (node (ref "C51") (pin "2") (pinfunction "2_2") (pintype "passive"))
      (node (ref "C53") (pin "2") (pinfunction "2_2") (pintype "passive"))
      (node (ref "J22") (pin "1") (pinfunction "1_1") (pintype "passive"))
      (node (ref "U21") (pin "4") (pinfunction "OUT_4") (pintype "passive"))
      (node (ref "U21") (pin "8") (pinfunction "OUT_8") (pintype "passive"))
    )
    (net (code "49") (name "/MOTOR_SUPPLY") (class "Default")
      (node (ref "C42") (pin "1") (pinfunction "1_1") (pintype "passive"))
      (node (ref "C43") (pin "1") (pinfunction "1_1") (pintype "passive"))
      (node (ref "C44") (pin "1") (pinfunction "1_1") (pintype "passive"))
      (node (ref "C45") (pin "2") (pinfunction "2_2") (pintype "passive"))
      (node (ref "C48") (pin "1") (pinfunction "1_1") (pintype "passive"))
      (node (ref "C49") (pin "1") (pinfunction "1_1") (pintype "passive"))
      (node (ref "C52") (pin "1") (pinfunction "1_1") (pintype "passive"))
      (node (ref "C53") (pin "1") (pinfunction "1_1") (pintype "passive"))
      (node (ref "C54") (pin "1") (pinfunction "1_1") (pintype "passive"))
      (node (ref "C55") (pin "2") (pinfunction "2_2") (pintype "passive"))
      (node (ref "C56") (pin "1") (pinfunction "1_1") (pintype "passive"))
      (node (ref "C57") (pin "2") (pinfunction "2_2") (pintype "passive"))
      (node (ref "D9") (pin "1") (pinfunction "CATHODE_1") (pintype "passive"))
      (node (ref "U16") (pin "7") (pinfunction "VS_7") (pintype "passive"))
      (node (ref "U17") (pin "7") (pinfunction "VS_7") (pintype "passive"))
      (node (ref "U18") (pin "7") (pinfunction "VS_7") (pintype "passive"))
      (node (ref "U19") (pin "7") (pinfunction "VS_7") (pintype "passive"))
      (node (ref "U20") (pin "7") (pinfunction "VS_7") (pintype "passive"))
      (node (ref "U21") (pin "7") (pinfunction "VS_7") (pintype "passive"))
      (node (ref "U24") (pin "3") (pinfunction "SOURCE_3") (pintype "passive"))
    )
    (net (code "50") (name "/RTS_FTDI") (class "Default")
      (node (ref "Q1") (pin "2") (pinfunction "E_2") (pintype "passive"))
      (node (ref "R14") (pin "2") (pinfunction "2_2") (pintype "passive"))
      (node (ref "U4") (pin "19") (pinfunction "~{RTS}_19") (pintype "passive"))
    )
    (net (code "51") (name "/RXD_FTDI") (class "Default")
      (node (ref "R9") (pin "2") (pinfunction "2_2") (pintype "passive"))
      (node (ref "U4") (pin "1") (pinfunction "RXD_1") (pintype "passive"))
    )
    (net (code "52") (name "/SCLK_Main") (class "Default")
      (node (ref "ESP32-S3-WROOM-1U-N16R8") (pin "29") (pinfunction "IO36_29") (pintype "passive"))
    )
    (net (code "53") (name "/TXD_FTDI") (class "Default")
      (node (ref "R10") (pin "1") (pinfunction "1_1") (pintype "passive"))
      (node (ref "U4") (pin "17") (pinfunction "TXD_17") (pintype "passive"))
    )
    (net (code "54") (name "/VBUS SENSE") (class "Default")
      (node (ref "R22") (pin "1") (pinfunction "1_1") (pintype "passive"))
      (node (ref "R26") (pin "2") (pinfunction "2_2") (pintype "passive"))
      (node (ref "U4") (pin "16") (pinfunction "CBUS3_16") (pintype "passive"))
    )
    (net (code "55") (name "BUCK_OUT") (class "Default")
      (node (ref "C18") (pin "1") (pinfunction "1_1") (pintype "passive"))
      (node (ref "C58") (pin "1") (pinfunction "1_1") (pintype "passive"))
      (node (ref "D13") (pin "1") (pinfunction "1_1") (pintype "passive"))
      (node (ref "J14") (pin "3") (pinfunction "3_3") (pintype "passive"))
      (node (ref "L1") (pin "2") (pinfunction "2_2") (pintype "passive"))
      (node (ref "R5") (pin "2") (pinfunction "2_2") (pintype "passive"))
    )
    (net (code "56") (name "GND") (class "Default")
      (node (ref "C1") (pin "1") (pinfunction "1_1") (pintype "passive"))
      (node (ref "C15") (pin "1") (pinfunction "1_1") (pintype "passive"))
      (node (ref "C16") (pin "1") (pinfunction "1_1") (pintype "passive"))
      (node (ref "C17") (pin "1") (pinfunction "1_1") (pintype "passive"))
      (node (ref "C18") (pin "2") (pinfunction "2_2") (pintype "passive"))
      (node (ref "C19") (pin "1") (pinfunction "1_1") (pintype "passive"))
      (node (ref "C2") (pin "1") (pinfunction "1_1") (pintype "passive"))
      (node (ref "C20") (pin "1") (pinfunction "1_1") (pintype "passive"))
      (node (ref "C21") (pin "1") (pinfunction "1_1") (pintype "passive"))
      (node (ref "C22") (pin "1") (pinfunction "1_1") (pintype "passive"))
      (node (ref "C23") (pin "1") (pinfunction "1_1") (pintype "passive"))
      (node (ref "C24") (pin "1") (pinfunction "1_1") (pintype "passive"))
      (node (ref "C25") (pin "1") (pinfunction "1_1") (pintype "passive"))
      (node (ref "C26") (pin "1") (pinfunction "1_1") (pintype "passive"))
      (node (ref "C27") (pin "1") (pinfunction "1_1") (pintype "passive"))
      (node (ref "C28") (pin "1") (pinfunction "1_1") (pintype "passive"))
      (node (ref "C29") (pin "1") (pinfunction "1_1") (pintype "passive"))
      (node (ref "C3") (pin "1") (pinfunction "1_1") (pintype "passive"))
      (node (ref "C30") (pin "1") (pinfunction "1_1") (pintype "passive"))
      (node (ref "C31") (pin "1") (pinfunction "1_1") (pintype "passive"))
      (node (ref "C32") (pin "1") (pinfunction "1_1") (pintype "passive"))
      (node (ref "C33") (pin "1") (pinfunction "1_1") (pintype "passive"))
      (node (ref "C34") (pin "1") (pinfunction "1_1") (pintype "passive"))
      (node (ref "C35") (pin "1") (pinfunction "1_1") (pintype "passive"))
      (node (ref "C36") (pin "1") (pinfunction "1_1") (pintype "passive"))
      (node (ref "C37") (pin "1") (pinfunction "1_1") (pintype "passive"))
      (node (ref "C38") (pin "1") (pinfunction "1_1") (pintype "passive"))
      (node (ref "C39") (pin "1") (pinfunction "1_1") (pintype "passive"))
      (node (ref "C4") (pin "1") (pinfunction "1_1") (pintype "passive"))
      (node (ref "C40") (pin "1") (pinfunction "1_1") (pintype "passive"))
      (node (ref "C41") (pin "1") (pinfunction "1_1") (pintype "passive"))
      (node (ref "C44") (pin "2") (pinfunction "2_2") (pintype "passive"))
      (node (ref "C45") (pin "1") (pinfunction "1_1") (pintype "passive"))
      (node (ref "C46") (pin "1") (pinfunction "1_1") (pintype "passive"))
      (node (ref "C47") (pin "1") (pinfunction "1_1") (pintype "passive"))
      (node (ref "C50") (pin "1") (pinfunction "1_1") (pintype "passive"))
      (node (ref "C51") (pin "1") (pinfunction "1_1") (pintype "passive"))
      (node (ref "C54") (pin "2") (pinfunction "2_2") (pintype "passive"))
      (node (ref "C55") (pin "1") (pinfunction "1_1") (pintype "passive"))
      (node (ref "C56") (pin "2") (pinfunction "2_2") (pintype "passive"))
      (node (ref "C57") (pin "1") (pinfunction "1_1") (pintype "passive"))
      (node (ref "C58") (pin "2") (pinfunction "2_2") (pintype "passive"))
      (node (ref "C6") (pin "1") (pinfunction "1_1") (pintype "passive"))
      (node (ref "C60") (pin "1") (pinfunction "1_1") (pintype "passive"))
      (node (ref "C61") (pin "1") (pinfunction "1_1") (pintype "passive"))
      (node (ref "D10") (pin "1") (pinfunction "1_1") (pintype "passive"))
      (node (ref "D11") (pin "1") (pinfunction "1_1") (pintype "passive"))
      (node (ref "D12") (pin "1") (pinfunction "1_1") (pintype "passive"))
      (node (ref "D13") (pin "2") (pinfunction "2_2") (pintype "passive"))
      (node (ref "D8") (pin "1") (pinfunction "1_1") (pintype "passive"))
      (node (ref "ESP32-S3-WROOM-1U-N16R8") (pin "1") (pinfunction "GND_1") (pintype "passive"))
      (node (ref "ESP32-S3-WROOM-1U-N16R8") (pin "40") (pinfunction "GND_40") (pintype "passive"))
      (node (ref "ESP32-S3-WROOM-1U-N16R8") (pin "41_1") (pinfunction "GND_41_1") (pintype "passive"))
      (node (ref "ESP32-S3-WROOM-1U-N16R8") (pin "41_2") (pinfunction "GND_41_2") (pintype "passive"))
      (node (ref "ESP32-S3-WROOM-1U-N16R8") (pin "41_3") (pinfunction "GND_41_3") (pintype "passive"))
      (node (ref "ESP32-S3-WROOM-1U-N16R8") (pin "41_4") (pinfunction "GND_41_4") (pintype "passive"))
      (node (ref "ESP32-S3-WROOM-1U-N16R8") (pin "41_5") (pinfunction "GND_41_5") (pintype "passive"))
      (node (ref "ESP32-S3-WROOM-1U-N16R8") (pin "41_6") (pinfunction "GND_41_6") (pintype "passive"))
      (node (ref "ESP32-S3-WROOM-1U-N16R8") (pin "41_7") (pinfunction "GND_41_7") (pintype "passive"))
      (node (ref "ESP32-S3-WROOM-1U-N16R8") (pin "41_8") (pinfunction "GND_41_8") (pintype "passive"))
      (node (ref "ESP32-S3-WROOM-1U-N16R8") (pin "41_9") (pinfunction "GND_41_9") (pintype "passive"))
      (node (ref "FB1") (pin "1") (pinfunction "1_1") (pintype "passive"))
      (node (ref "J13") (pin "1") (pinfunction "1_1") (pintype "passive"))
      (node (ref "J17") (pin "1") (pinfunction "1_1") (pintype "passive"))
      (node (ref "J18") (pin "A1B12") (pinfunction "GND_A1B12_A1B12") (pintype "passive"))
      (node (ref "J18") (pin "B1A12") (pinfunction "GND_B1A12_B1A12") (pintype "passive"))
      (node (ref "J18") (pin "S1") (pinfunction "SHIELD_1_S1") (pintype "passive"))
      (node (ref "J18") (pin "S2") (pinfunction "SHIELD_2_S2") (pintype "passive"))
      (node (ref "J18") (pin "S3") (pinfunction "SHIELD_3_S3") (pintype "passive"))
      (node (ref "J18") (pin "S4") (pinfunction "SHIELD_4_S4") (pintype "passive"))
      (node (ref "J3") (pin "1") (pinfunction "1_1") (pintype "passive"))
      (node (ref "J3") (pin "5") (pinfunction "5_5") (pintype "passive"))
      (node (ref "J4") (pin "1") (pinfunction "1_1") (pintype "passive"))
      (node (ref "J4") (pin "5") (pinfunction "5_5") (pintype "passive"))
      (node (ref "J5") (pin "1") (pinfunction "1_1") (pintype "passive"))
      (node (ref "J5") (pin "5") (pinfunction "5_5") (pintype "passive"))
      (node (ref "J6") (pin "5") (pinfunction "5_5") (pintype "passive"))
      (node (ref "J7") (pin "5") (pinfunction "5_5") (pintype "passive"))
      (node (ref "R18") (pin "1") (pinfunction "1_1") (pintype "passive"))
      (node (ref "R23") (pin "1") (pinfunction "1_1") (pintype "passive"))
      (node (ref "R24") (pin "1") (pinfunction "1_1") (pintype "passive"))
      (node (ref "R25") (pin "1") (pinfunction "1_1") (pintype "passive"))
      (node (ref "R26") (pin "1") (pinfunction "1_1") (pintype "passive"))
      (node (ref "R27") (pin "1") (pinfunction "1_1") (pintype "passive"))
      (node (ref "R28") (pin "1") (pinfunction "1_1") (pintype "passive"))
      (node (ref "R29") (pin "1") (pinfunction "1_1") (pintype "passive"))
      (node (ref "R30") (pin "1") (pinfunction "1_1") (pintype "passive"))
      (node (ref "R31") (pin "1") (pinfunction "1_1") (pintype "passive"))
      (node (ref "R32") (pin "1") (pinfunction "1_1") (pintype "passive"))
      (node (ref "R33") (pin "1") (pinfunction "1_1") (pintype "passive"))
      (node (ref "R34") (pin "1") (pinfunction "1_1") (pintype "passive"))
      (node (ref "R35") (pin "1") (pinfunction "1_1") (pintype "passive"))
      (node (ref "R36") (pin "1") (pinfunction "1_1") (pintype "passive"))
      (node (ref "R37") (pin "1") (pinfunction "1_1") (pintype "passive"))
      (node (ref "R38") (pin "1") (pinfunction "1_1") (pintype "passive"))
      (node (ref "R39") (pin "1") (pinfunction "1_1") (pintype "passive"))
      (node (ref "R40") (pin "1") (pinfunction "1_1") (pintype "passive"))
      (node (ref "R41") (pin "1") (pinfunction "1_1") (pintype "passive"))
      (node (ref "R42") (pin "1") (pinfunction "1_1") (pintype "passive"))
      (node (ref "R43") (pin "1") (pinfunction "1_1") (pintype "passive"))
      (node (ref "R44") (pin "1") (pinfunction "1_1") (pintype "passive"))
      (node (ref "R45") (pin "1") (pinfunction "1_1") (pintype "passive"))
      (node (ref "R46") (pin "1") (pinfunction "1_1") (pintype "passive"))
      (node (ref "R47") (pin "1") (pinfunction "1_1") (pintype "passive"))
      (node (ref "R48") (pin "1") (pinfunction "1_1") (pintype "passive"))
      (node (ref "R49") (pin "1") (pinfunction "1_1") (pintype "passive"))
      (node (ref "R50") (pin "1") (pinfunction "1_1") (pintype "passive"))
      (node (ref "SW2") (pin "3") (pinfunction "3_3") (pintype "passive"))
      (node (ref "SW2") (pin "4") (pinfunction "4_4") (pintype "passive"))
      (node (ref "SW3") (pin "3") (pinfunction "3_3") (pintype "passive"))
      (node (ref "SW3") (pin "4") (pinfunction "4_4") (pintype "passive"))
      (node (ref "U1") (pin "1") (pinfunction "1_1") (pintype "passive"))
      (node (ref "U10") (pin "3") (pinfunction "GND_3") (pintype "power_in"))
      (node (ref "U11") (pin "3") (pinfunction "GND_3") (pintype "power_in"))
      (node (ref "U12") (pin "3") (pinfunction "GND_3") (pintype "power_in"))
      (node (ref "U13") (pin "3") (pinfunction "GND_3") (pintype "power_in"))
      (node (ref "U14") (pin "3") (pinfunction "GND_3") (pintype "power_in"))
      (node (ref "U15") (pin "3") (pinfunction "GND_3") (pintype "power_in"))
      (node (ref "U16") (pin "1") (pinfunction "GND_1") (pintype "power_in"))
      (node (ref "U17") (pin "1") (pinfunction "GND_1") (pintype "power_in"))
      (node (ref "U18") (pin "1") (pinfunction "GND_1") (pintype "power_in"))
      (node (ref "U19") (pin "1") (pinfunction "GND_1") (pintype "power_in"))
      (node (ref "U20") (pin "1") (pinfunction "GND_1") (pintype "power_in"))
      (node (ref "U21") (pin "1") (pinfunction "GND_1") (pintype "power_in"))
      (node (ref "U25") (pin "1") (pinfunction "GND_1") (pintype "passive"))
      (node (ref "U25") (pin "16") (pinfunction "GND_16") (pintype "passive"))
      (node (ref "U25") (pin "2") (pinfunction "GND_2") (pintype "passive"))
      (node (ref "U25") (pin "9") (pinfunction "GND_9") (pintype "passive"))
      (node (ref "U3") (pin "2") (pinfunction "GND_2") (pintype "power_in"))
      (node (ref "U3") (pin "4") (pinfunction "GND_4") (pintype "power_in"))
      (node (ref "U4") (pin "13") (pinfunction "GND_13") (pintype "passive"))
      (node (ref "U4") (pin "21") (pinfunction "GND_21") (pintype "passive"))
      (node (ref "U4") (pin "3") (pinfunction "GND_3") (pintype "passive"))
      (node (ref "U7") (pin "3") (pinfunction "GND_3") (pintype "power_in"))
      (node (ref "U8") (pin "3") (pinfunction "GND_3") (pintype "power_in"))
      (node (ref "U9") (pin "3") (pinfunction "GND_3") (pintype "power_in"))
    )
    (net (code "57") (name "Net-(C5-Pad1)") (class "Default")
      (node (ref "C5") (pin "1") (pinfunction "1_1") (pintype "passive"))
      (node (ref "U1") (pin "6") (pinfunction "6_6") (pintype "passive"))
    )
    (net (code "58") (name "Net-(C5-Pad2)") (class "Default")
      (node (ref "C5") (pin "2") (pinfunction "2_2") (pintype "passive"))
      (node (ref "L1") (pin "1") (pinfunction "1_1") (pintype "passive"))
      (node (ref "U1") (pin "2") (pinfunction "2_2") (pintype "passive"))
    )
    (net (code "59") (name "Net-(D7-Pad2)") (class "Default")
      (node (ref "D7") (pin "2") (pinfunction "2_2") (pintype "passive"))
      (node (ref "R3") (pin "1") (pinfunction "1_1") (pintype "passive"))
    )
    (net (code "60") (name "Net-(D8-Pad2)") (class "Default")
      (node (ref "D8") (pin "2") (pinfunction "2_2") (pintype "passive"))
      (node (ref "R2") (pin "1") (pinfunction "1_1") (pintype "passive"))
    )
    (net (code "61") (name "Net-(D9-ANODE)") (class "Default")
      (node (ref "D9") (pin "2") (pinfunction "ANODE_2") (pintype "passive"))
      (node (ref "R25") (pin "2") (pinfunction "2_2") (pintype "passive"))
      (node (ref "U24") (pin "1") (pinfunction "GATE_1") (pintype "passive"))
    )
    (net (code "62") (name "Net-(ESP32-S3-WROOM-1U-N16R8-IO0)") (class "Default")
      (node (ref "ESP32-S3-WROOM-1U-N16R8") (pin "27") (pinfunction "IO0_27") (pintype "passive"))
      (node (ref "R12") (pin "1") (pinfunction "1_1") (pintype "passive"))
    )
    (net (code "63") (name "Net-(ESP32-S3-WROOM-1U-N16R8-IO11)") (class "Default")
      (node (ref "ESP32-S3-WROOM-1U-N16R8") (pin "19") (pinfunction "IO11_19") (pintype "passive"))
      (node (ref "R58") (pin "2") (pinfunction "2_2") (pintype "passive"))
    )
    (net (code "64") (name "Net-(ESP32-S3-WROOM-1U-N16R8-IO12)") (class "Default")
      (node (ref "ESP32-S3-WROOM-1U-N16R8") (pin "20") (pinfunction "IO12_20") (pintype "passive"))
      (node (ref "R59") (pin "2") (pinfunction "2_2") (pintype "passive"))
    )
    (net (code "65") (name "Net-(ESP32-S3-WROOM-1U-N16R8-IO37)") (class "Default")
      (node (ref "ESP32-S3-WROOM-1U-N16R8") (pin "30") (pinfunction "IO37_30") (pintype "passive"))
      (node (ref "R16") (pin "1") (pinfunction "1_1") (pintype "passive"))
    )
    (net (code "66") (name "Net-(ESP32-S3-WROOM-1U-N16R8-RXD0)") (class "Default")
      (node (ref "ESP32-S3-WROOM-1U-N16R8") (pin "36") (pinfunction "RXD0_36") (pintype "passive"))
      (node (ref "R10") (pin "2") (pinfunction "2_2") (pintype "passive"))
    )
    (net (code "67") (name "Net-(ESP32-S3-WROOM-1U-N16R8-TXD0)") (class "Default")
      (node (ref "ESP32-S3-WROOM-1U-N16R8") (pin "37") (pinfunction "TXD0_37") (pintype "passive"))
      (node (ref "R9") (pin "1") (pinfunction "1_1") (pintype "passive"))
    )
    (net (code "68") (name "Net-(F1-Pad1)") (class "Default")
      (node (ref "F1") (pin "1") (pinfunction "1_1") (pintype "passive"))
      (node (ref "J13") (pin "2") (pinfunction "2_2") (pintype "passive"))
    )
    (net (code "69") (name "Net-(F2-Pad1)") (class "Default")
      (node (ref "F2") (pin "1") (pinfunction "1_1") (pintype "passive"))
      (node (ref "J17") (pin "2") (pinfunction "2_2") (pintype "passive"))
    )
    (net (code "70") (name "Net-(J18-CC1)") (class "Default")
      (node (ref "J18") (pin "A5") (pinfunction "CC1_A5") (pintype "passive"))
      (node (ref "R24") (pin "2") (pinfunction "2_2") (pintype "passive"))
    )
    (net (code "71") (name "Net-(J18-CC2)") (class "Default")
      (node (ref "J18") (pin "B5") (pinfunction "CC2_B5") (pintype "passive"))
      (node (ref "R23") (pin "2") (pinfunction "2_2") (pintype "passive"))
    )
    (net (code "72") (name "Net-(Q1-B)") (class "Default")
      (node (ref "Q1") (pin "1") (pinfunction "B_1") (pintype "passive"))
      (node (ref "R13") (pin "1") (pinfunction "1_1") (pintype "passive"))
    )
    (net (code "73") (name "Net-(Q2-B)") (class "Default")
      (node (ref "Q2") (pin "1") (pinfunction "B_1") (pintype "passive"))
      (node (ref "R14") (pin "1") (pinfunction "1_1") (pintype "passive"))
    )
    (net (code "74") (name "Net-(R18-Pad2)") (class "Default")
      (node (ref "R18") (pin "2") (pinfunction "2_2") (pintype "passive"))
      (node (ref "R5") (pin "1") (pinfunction "1_1") (pintype "passive"))
      (node (ref "U1") (pin "4") (pinfunction "4_4") (pintype "passive"))
    )
    (net (code "75") (name "Net-(U10-B)") (class "Default")
      (node (ref "U10") (pin "2") (pinfunction "B_2") (pintype "passive"))
      (node (ref "U14") (pin "4") (pinfunction "Y_4") (pintype "passive"))
    )
    (net (code "76") (name "Net-(U12-B)") (class "Default")
      (node (ref "U12") (pin "2") (pinfunction "B_2") (pintype "passive"))
      (node (ref "U15") (pin "4") (pinfunction "Y_4") (pintype "passive"))
    )
    (net (code "77") (name "Net-(U13-Y)") (class "Default")
      (node (ref "U13") (pin "4") (pinfunction "Y_4") (pintype "passive"))
      (node (ref "U8") (pin "2") (pinfunction "B_2") (pintype "passive"))
    )
    (net (code "78") (name "Net-(U16-INH)") (class "Default")
      (node (ref "R51") (pin "2") (pinfunction "2_2") (pintype "passive"))
      (node (ref "U16") (pin "3") (pinfunction "INH_3") (pintype "passive"))
    )
    (net (code "79") (name "Net-(U16-IS)") (class "Default")
      (node (ref "R39") (pin "2") (pinfunction "2_2") (pintype "passive"))
      (node (ref "U16") (pin "6") (pinfunction "IS_6") (pintype "passive"))
    )
    (net (code "80") (name "Net-(U16-SR)") (class "Default")
      (node (ref "C33") (pin "2") (pinfunction "2_2") (pintype "passive"))
      (node (ref "R45") (pin "2") (pinfunction "2_2") (pintype "passive"))
      (node (ref "U16") (pin "5") (pinfunction "SR_5") (pintype "passive"))
    )
    (net (code "81") (name "Net-(U17-INH)") (class "Default")
      (node (ref "R52") (pin "2") (pinfunction "2_2") (pintype "passive"))
      (node (ref "U17") (pin "3") (pinfunction "INH_3") (pintype "passive"))
    )
    (net (code "82") (name "Net-(U17-IS)") (class "Default")
      (node (ref "R40") (pin "2") (pinfunction "2_2") (pintype "passive"))
      (node (ref "U17") (pin "6") (pinfunction "IS_6") (pintype "passive"))
    )
    (net (code "83") (name "Net-(U17-SR)") (class "Default")
      (node (ref "C34") (pin "2") (pinfunction "2_2") (pintype "passive"))
      (node (ref "R46") (pin "2") (pinfunction "2_2") (pintype "passive"))
      (node (ref "U17") (pin "5") (pinfunction "SR_5") (pintype "passive"))
    )
    (net (code "84") (name "Net-(U18-INH)") (class "Default")
      (node (ref "R53") (pin "2") (pinfunction "2_2") (pintype "passive"))
      (node (ref "U18") (pin "3") (pinfunction "INH_3") (pintype "passive"))
    )
    (net (code "85") (name "Net-(U18-IS)") (class "Default")
      (node (ref "R41") (pin "2") (pinfunction "2_2") (pintype "passive"))
      (node (ref "U18") (pin "6") (pinfunction "IS_6") (pintype "passive"))
    )
    (net (code "86") (name "Net-(U18-SR)") (class "Default")
      (node (ref "C35") (pin "2") (pinfunction "2_2") (pintype "passive"))
      (node (ref "R47") (pin "2") (pinfunction "2_2") (pintype "passive"))
      (node (ref "U18") (pin "5") (pinfunction "SR_5") (pintype "passive"))
    )
    (net (code "87") (name "Net-(U19-INH)") (class "Default")
      (node (ref "R54") (pin "2") (pinfunction "2_2") (pintype "passive"))
      (node (ref "U19") (pin "3") (pinfunction "INH_3") (pintype "passive"))
    )
    (net (code "88") (name "Net-(U19-IS)") (class "Default")
      (node (ref "R42") (pin "2") (pinfunction "2_2") (pintype "passive"))
      (node (ref "U19") (pin "6") (pinfunction "IS_6") (pintype "passive"))
    )
    (net (code "89") (name "Net-(U19-SR)") (class "Default")
      (node (ref "C36") (pin "2") (pinfunction "2_2") (pintype "passive"))
      (node (ref "R48") (pin "2") (pinfunction "2_2") (pintype "passive"))
      (node (ref "U19") (pin "5") (pinfunction "SR_5") (pintype "passive"))
    )
    (net (code "90") (name "Net-(U20-INH)") (class "Default")
      (node (ref "R55") (pin "2") (pinfunction "2_2") (pintype "passive"))
      (node (ref "U20") (pin "3") (pinfunction "INH_3") (pintype "passive"))
    )
    (net (code "91") (name "Net-(U20-IS)") (class "Default")
      (node (ref "R43") (pin "2") (pinfunction "2_2") (pintype "passive"))
      (node (ref "U20") (pin "6") (pinfunction "IS_6") (pintype "passive"))
    )
    (net (code "92") (name "Net-(U20-SR)") (class "Default")
      (node (ref "C37") (pin "2") (pinfunction "2_2") (pintype "passive"))
      (node (ref "R49") (pin "2") (pinfunction "2_2") (pintype "passive"))
      (node (ref "U20") (pin "5") (pinfunction "SR_5") (pintype "passive"))
    )
    (net (code "93") (name "Net-(U21-INH)") (class "Default")
      (node (ref "R56") (pin "2") (pinfunction "2_2") (pintype "passive"))
      (node (ref "U21") (pin "3") (pinfunction "INH_3") (pintype "passive"))
    )
    (net (code "94") (name "Net-(U21-IS)") (class "Default")
      (node (ref "R44") (pin "2") (pinfunction "2_2") (pintype "passive"))
      (node (ref "U21") (pin "6") (pinfunction "IS_6") (pintype "passive"))
    )
    (net (code "95") (name "Net-(U21-SR)") (class "Default")
      (node (ref "C38") (pin "2") (pinfunction "2_2") (pintype "passive"))
      (node (ref "R50") (pin "2") (pinfunction "2_2") (pintype "passive"))
      (node (ref "U21") (pin "5") (pinfunction "SR_5") (pintype "passive"))
    )
    (net (code "96") (name "Net-(U25-MISO)") (class "Default")
      (node (ref "R15") (pin "1") (pinfunction "1_1") (pintype "passive"))
      (node (ref "U25") (pin "13") (pinfunction "MISO_13") (pintype "passive"))
    )
    (net (code "97") (name "PWR") (class "Default")
      (node (ref "C17") (pin "2") (pinfunction "2_2") (pintype "passive"))
      (node (ref "C39") (pin "2") (pinfunction "2_2") (pintype "passive"))
      (node (ref "F1") (pin "2") (pinfunction "2_2") (pintype "passive"))
      (node (ref "F2") (pin "2") (pinfunction "2_2") (pintype "passive"))
      (node (ref "U1") (pin "3") (pinfunction "3_3") (pintype "passive"))
      (node (ref "U1") (pin "5") (pinfunction "5_5") (pintype "passive"))
      (node (ref "U24") (pin "2") (pinfunction "DRAIN_2") (pintype "passive"))
    )
    (net (code "98") (name "unconnected-(ESP32-S3-WROOM-1U-N16R8-IO19{slash}USB_D--Pad13)") (class "Default")
      (node (ref "ESP32-S3-WROOM-1U-N16R8") (pin "13") (pinfunction "IO19/USB_D-_13") (pintype "passive+no_connect"))
    )
    (net (code "99") (name "unconnected-(ESP32-S3-WROOM-1U-N16R8-IO20{slash}USB_D+-Pad14)") (class "Default")
      (node (ref "ESP32-S3-WROOM-1U-N16R8") (pin "14") (pinfunction "IO20/USB_D+_14") (pintype "passive+no_connect"))
    )
    (net (code "100") (name "unconnected-(ESP32-S3-WROOM-1U-N16R8-IO21-Pad23)") (class "Default")
      (node (ref "ESP32-S3-WROOM-1U-N16R8") (pin "23") (pinfunction "IO21_23") (pintype "passive+no_connect"))
    )
    (net (code "101") (name "unconnected-(ESP32-S3-WROOM-1U-N16R8-IO39-Pad32)") (class "Default")
      (node (ref "ESP32-S3-WROOM-1U-N16R8") (pin "32") (pinfunction "IO39_32") (pintype "passive+no_connect"))
    )
    (net (code "102") (name "unconnected-(ESP32-S3-WROOM-1U-N16R8-IO40-Pad33)") (class "Default")
      (node (ref "ESP32-S3-WROOM-1U-N16R8") (pin "33") (pinfunction "IO40_33") (pintype "passive+no_connect"))
    )
    (net (code "103") (name "unconnected-(ESP32-S3-WROOM-1U-N16R8-IO41-Pad34)") (class "Default")
      (node (ref "ESP32-S3-WROOM-1U-N16R8") (pin "34") (pinfunction "IO41_34") (pintype "passive+no_connect"))
    )
    (net (code "104") (name "unconnected-(ESP32-S3-WROOM-1U-N16R8-IO42-Pad35)") (class "Default")
      (node (ref "ESP32-S3-WROOM-1U-N16R8") (pin "35") (pinfunction "IO42_35") (pintype "passive+no_connect"))
    )
    (net (code "105") (name "unconnected-(ESP32-S3-WROOM-1U-N16R8-IO45-Pad26)") (class "Default")
      (node (ref "ESP32-S3-WROOM-1U-N16R8") (pin "26") (pinfunction "IO45_26") (pintype "passive+no_connect"))
    )
    (net (code "106") (name "unconnected-(ESP32-S3-WROOM-1U-N16R8-IO46-Pad16)") (class "Default")
      (node (ref "ESP32-S3-WROOM-1U-N16R8") (pin "16") (pinfunction "IO46_16") (pintype "passive+no_connect"))
    )
    (net (code "107") (name "unconnected-(J18-SBU1-PadA8)") (class "Default")
      (node (ref "J18") (pin "A8") (pinfunction "SBU1_A8") (pintype "passive+no_connect"))
    )
    (net (code "108") (name "unconnected-(J18-SBU2-PadB8)") (class "Default")
      (node (ref "J18") (pin "B8") (pinfunction "SBU2_B8") (pintype "passive+no_connect"))
    )
    (net (code "109") (name "unconnected-(U4-CBUS0-Pad15)") (class "Default")
      (node (ref "U4") (pin "15") (pinfunction "CBUS0_15") (pintype "passive+no_connect"))
    )
    (net (code "110") (name "unconnected-(U4-CBUS1-Pad14)") (class "Default")
      (node (ref "U4") (pin "14") (pinfunction "CBUS1_14") (pintype "passive+no_connect"))
    )
    (net (code "111") (name "unconnected-(U4-CBUS2-Pad7)") (class "Default")
      (node (ref "U4") (pin "7") (pinfunction "CBUS2_7") (pintype "passive+no_connect"))
    )
    (net (code "112") (name "unconnected-(U4-~{CTS}-Pad6)") (class "Default")
      (node (ref "U4") (pin "6") (pinfunction "~{CTS}_6") (pintype "passive+no_connect"))
    )
    (net (code "113") (name "unconnected-(U4-~{DCD}-Pad5)") (class "Default")
      (node (ref "U4") (pin "5") (pinfunction "~{DCD}_5") (pintype "passive+no_connect"))
    )
    (net (code "114") (name "unconnected-(U4-~{DSR}-Pad4)") (class "Default")
      (node (ref "U4") (pin "4") (pinfunction "~{DSR}_4") (pintype "passive+no_connect"))
    )
    (net (code "115") (name "unconnected-(U4-~{RI}-Pad2)") (class "Default")
      (node (ref "U4") (pin "2") (pinfunction "~{RI}_2") (pintype "passive+no_connect"))
    )
    (net (code "116") (name "unconnected-(U13-NC-Pad1)") (class "Default")
      (node (ref "U13") (pin "1") (pinfunction "NC_1") (pintype "passive+no_connect"))
    )
    (net (code "117") (name "unconnected-(U14-NC-Pad1)") (class "Default")
      (node (ref "U14") (pin "1") (pinfunction "NC_1") (pintype "passive+no_connect"))
    )
    (net (code "118") (name "unconnected-(U15-NC-Pad1)") (class "Default")
      (node (ref "U15") (pin "1") (pinfunction "NC_1") (pintype "passive+no_connect"))
    )
    (net (code "119") (name "unconnected-(U25-DIO1-Pad6)") (class "Default")
      (node (ref "U25") (pin "6") (pinfunction "DIO1_6") (pintype "passive+no_connect"))
    )
    (net (code "120") (name "unconnected-(U25-DIO2-Pad7)") (class "Default")
      (node (ref "U25") (pin "7") (pinfunction "DIO2_7") (pintype "passive+no_connect"))
    )
    (net (code "121") (name "unconnected-(U25-DIO3-Pad8)") (class "Default")
      (node (ref "U25") (pin "8") (pinfunction "DIO3_8") (pintype "passive+no_connect"))
    )
    (net (code "122") (name "unconnected-(U25-DIO4-Pad10)") (class "Default")
      (node (ref "U25") (pin "10") (pinfunction "DIO4_10") (pintype "passive+no_connect"))
    )
    (net (code "123") (name "unconnected-(U25-DIO5-Pad11)") (class "Default")
      (node (ref "U25") (pin "11") (pinfunction "DIO5_11") (pintype "passive+no_connect"))
    )
  )
)
